# madiz_plate_sheet_v3_2.net
KiCad netlist of a schematic drawn in Altium Designer
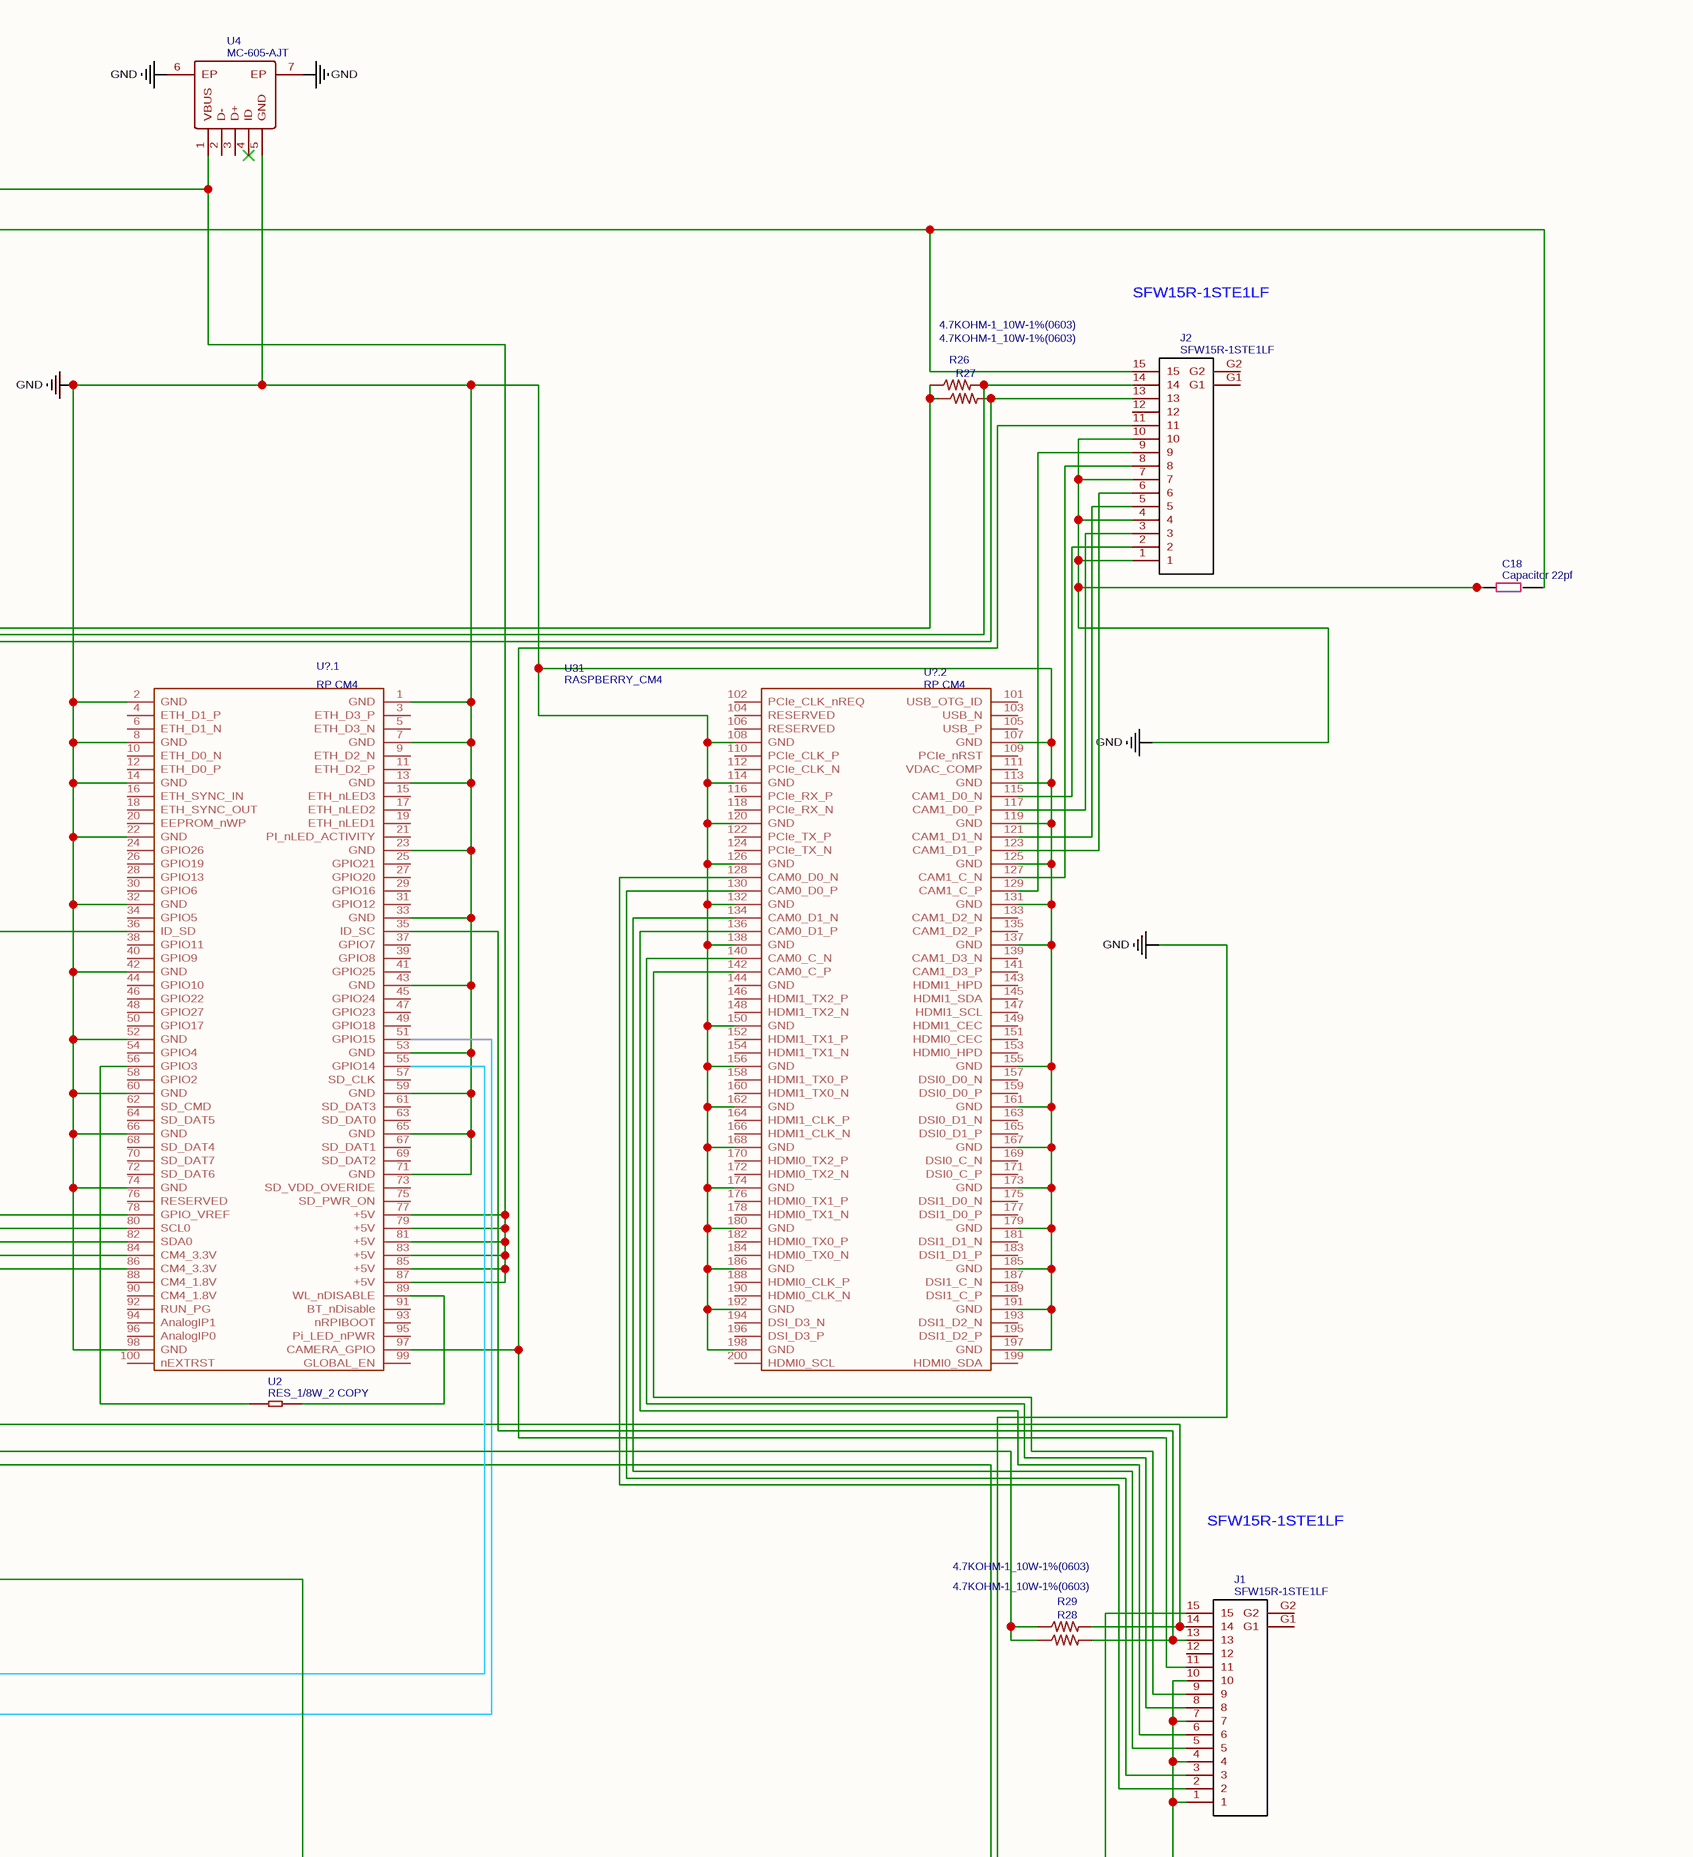
[diagram p0: madiz_plate_sheet_v3_2.schdoc, top right]
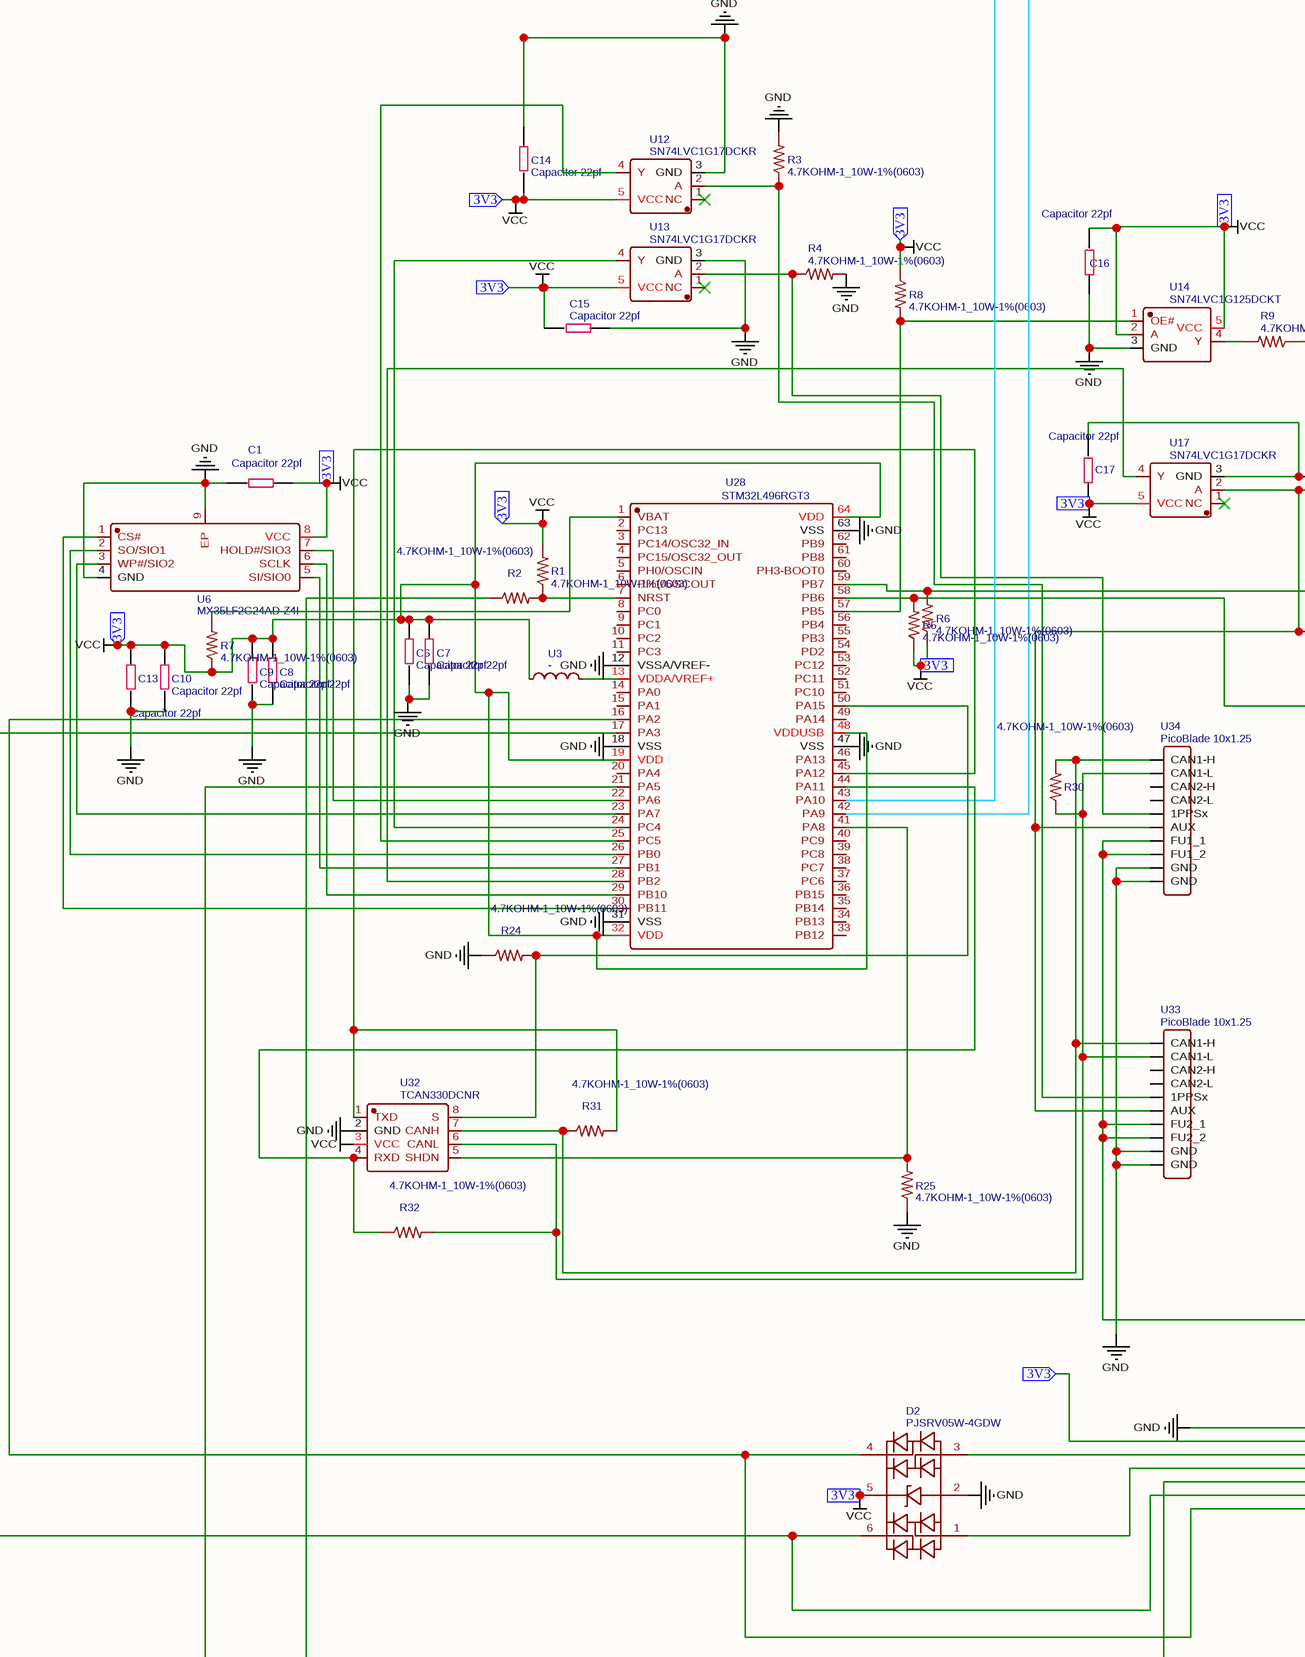
[diagram p1: madiz_plate_sheet_v3_2.schdoc, bottom left]
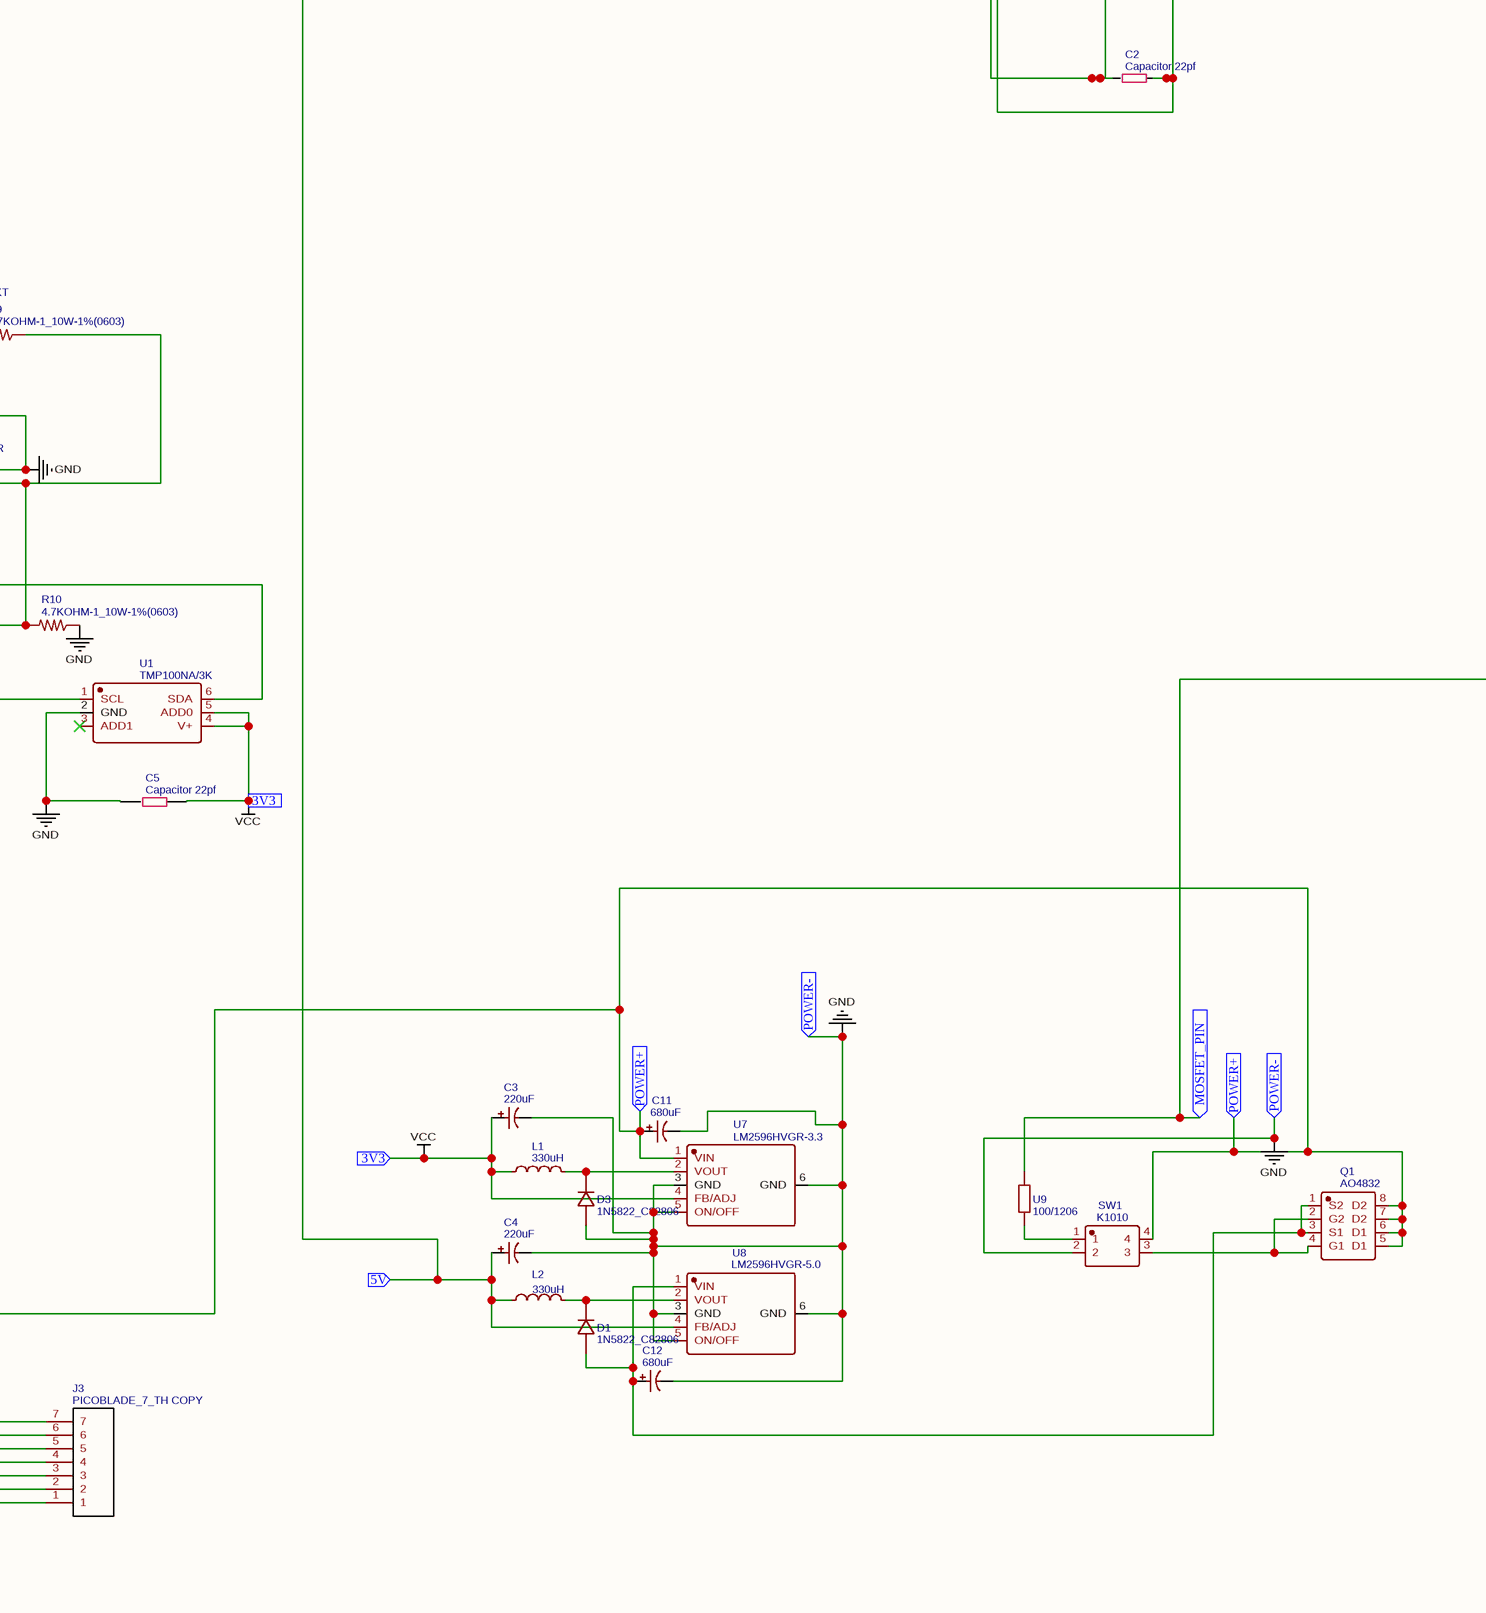
[diagram p2: madiz_plate_sheet_v3_2.schdoc, bottom right]

(export (version "E")
  (design (tool "Eeschema 10.0.6"))
  (components
    (comp (ref "C1")
      (value "Capacitor 22pf")
      (fields
        (field (name "MANUFACTURER") "KEMET")
        (field (name "MANUFACTURER PART") "C0805C220J5GACTU")
        (field (name "CONTRIBUTOR") "Tanay")
      )
      (libsource (lib "altium-import") (part "root_2_Capacitor 22pf_"))
    )
    (comp (ref "C2")
      (value "Capacitor 22pf")
      (fields
        (field (name "MANUFACTURER") "KEMET")
        (field (name "MANUFACTURER PART") "C0805C220J5GACTU")
        (field (name "CONTRIBUTOR") "Tanay")
      )
      (libsource (lib "altium-import") (part "root_2_Capacitor 22pf_"))
    )
    (comp (ref "C3")
      (value "220uF")
      (fields
        (field (name "MANUFACTURER") "CX(承兴)")
        (field (name "MANUFACTURER PART") "KS227M016F07RR0VH2FP0")
      )
      (libsource (lib "altium-import") (part "root_0_220uF_"))
    )
    (comp (ref "C4")
      (value "220uF")
      (fields
        (field (name "MANUFACTURER") "CX(承兴)")
        (field (name "MANUFACTURER PART") "KS227M016F07RR0VH2FP0")
      )
      (libsource (lib "altium-import") (part "root_0_220uF_"))
    )
    (comp (ref "C5")
      (value "Capacitor 22pf")
      (fields
        (field (name "MANUFACTURER") "KEMET")
        (field (name "MANUFACTURER PART") "C0805C220J5GACTU")
        (field (name "CONTRIBUTOR") "Tanay")
      )
      (libsource (lib "altium-import") (part "root_2_Capacitor 22pf_"))
    )
    (comp (ref "C6")
      (value "Capacitor 22pf")
      (fields
        (field (name "MANUFACTURER") "KEMET")
        (field (name "MANUFACTURER PART") "C0805C220J5GACTU")
        (field (name "CONTRIBUTOR") "Tanay")
      )
      (libsource (lib "altium-import") (part "root_3_Capacitor 22pf_"))
    )
    (comp (ref "C7")
      (value "Capacitor 22pf")
      (fields
        (field (name "MANUFACTURER") "KEMET")
        (field (name "MANUFACTURER PART") "C0805C220J5GACTU")
        (field (name "CONTRIBUTOR") "Tanay")
      )
      (libsource (lib "altium-import") (part "root_3_Capacitor 22pf_"))
    )
    (comp (ref "C8")
      (value "Capacitor 22pf")
      (fields
        (field (name "MANUFACTURER") "KEMET")
        (field (name "MANUFACTURER PART") "C0805C220J5GACTU")
        (field (name "CONTRIBUTOR") "Tanay")
      )
      (libsource (lib "altium-import") (part "root_3_Capacitor 22pf_"))
    )
    (comp (ref "C9")
      (value "Capacitor 22pf")
      (fields
        (field (name "MANUFACTURER") "KEMET")
        (field (name "MANUFACTURER PART") "C0805C220J5GACTU")
        (field (name "CONTRIBUTOR") "Tanay")
      )
      (libsource (lib "altium-import") (part "root_3_Capacitor 22pf_"))
    )
    (comp (ref "C10")
      (value "Capacitor 22pf")
      (fields
        (field (name "MANUFACTURER") "KEMET")
        (field (name "MANUFACTURER PART") "C0805C220J5GACTU")
        (field (name "CONTRIBUTOR") "Tanay")
      )
      (libsource (lib "altium-import") (part "root_3_Capacitor 22pf_"))
    )
    (comp (ref "C11")
      (value "680uF")
      (fields
        (field (name "MANUFACTURER") "CX(承兴)")
        (field (name "MANUFACTURER PART") "GR687M016F16RR0VL4FP0")
      )
      (libsource (lib "altium-import") (part "root_0_680uF_"))
    )
    (comp (ref "C12")
      (value "680uF")
      (fields
        (field (name "MANUFACTURER") "CX(承兴)")
        (field (name "MANUFACTURER PART") "GR687M016F16RR0VL4FP0")
      )
      (libsource (lib "altium-import") (part "root_0_680uF_"))
    )
    (comp (ref "C13")
      (value "Capacitor 22pf")
      (fields
        (field (name "MANUFACTURER") "KEMET")
        (field (name "MANUFACTURER PART") "C0805C220J5GACTU")
        (field (name "CONTRIBUTOR") "Tanay")
      )
      (libsource (lib "altium-import") (part "root_3_Capacitor 22pf_"))
    )
    (comp (ref "C14")
      (value "Capacitor 22pf")
      (fields
        (field (name "MANUFACTURER") "KEMET")
        (field (name "MANUFACTURER PART") "C0805C220J5GACTU")
        (field (name "CONTRIBUTOR") "Tanay")
      )
      (libsource (lib "altium-import") (part "root_3_Capacitor 22pf_"))
    )
    (comp (ref "C15")
      (value "Capacitor 22pf")
      (fields
        (field (name "MANUFACTURER") "KEMET")
        (field (name "MANUFACTURER PART") "C0805C220J5GACTU")
        (field (name "CONTRIBUTOR") "Tanay")
      )
      (libsource (lib "altium-import") (part "root_2_Capacitor 22pf_"))
    )
    (comp (ref "C16")
      (value "Capacitor 22pf")
      (fields
        (field (name "MANUFACTURER") "KEMET")
        (field (name "MANUFACTURER PART") "C0805C220J5GACTU")
        (field (name "CONTRIBUTOR") "Tanay")
      )
      (libsource (lib "altium-import") (part "root_1_Capacitor 22pf_"))
    )
    (comp (ref "C17")
      (value "Capacitor 22pf")
      (fields
        (field (name "MANUFACTURER") "KEMET")
        (field (name "MANUFACTURER PART") "C0805C220J5GACTU")
        (field (name "CONTRIBUTOR") "Tanay")
      )
      (libsource (lib "altium-import") (part "root_1_Capacitor 22pf_"))
    )
    (comp (ref "C18")
      (value "Capacitor 22pf")
      (fields
        (field (name "MANUFACTURER") "KEMET")
        (field (name "MANUFACTURER PART") "C0805C220J5GACTU")
        (field (name "CONTRIBUTOR") "Tanay")
      )
      (libsource (lib "altium-import") (part "root_0_Capacitor 22pf_"))
    )
    (comp (ref "D1")
      (value "1N5822_C82806")
      (fields (field (name "MANUFACTURER") "LRC(乐山无线电)") (field (name "MANUFACTURER PART") "1N5822"))
      (libsource (lib "altium-import") (part "root_3_1N5822_C82806_"))
    )
    (comp (ref "D2")
      (value "PJSRV05W-4GDW")
      (fields
        (field (name "MANUFACTURER") "PANJIT(强茂)")
        (field (name "MANUFACTURER PART") "PJSRV05W-4GDW_R1_00001")
        (field (name "CONTRIBUTOR") "LCSC")
      )
      (libsource (lib "altium-import") (part "root_1_PJSRV05W-4GDW_"))
    )
    (comp (ref "D3")
      (value "1N5822_C82806")
      (fields (field (name "MANUFACTURER") "LRC(乐山无线电)") (field (name "MANUFACTURER PART") "1N5822"))
      (libsource (lib "altium-import") (part "root_3_1N5822_C82806_"))
    )
    (comp (ref "J1")
      (value "SFW15R-1STE1LF")
      (fields (field (name "MANUFACTURER") "Amphenol FCI") (field (name "CONTRIBUTOR") "pietlgo221"))
      (libsource (lib "altium-import") (part "root_2_SFW15R-1STE1LF_"))
    )
    (comp (ref "J2")
      (value "SFW15R-1STE1LF")
      (fields (field (name "MANUFACTURER") "Amphenol FCI") (field (name "CONTRIBUTOR") "pietlgo221"))
      (libsource (lib "altium-import") (part "root_2_SFW15R-1STE1LF_"))
    )
    (comp (ref "J3")
      (value "PICOBLADE_7_TH COPY")
      (fields (field (name "MANUFACTURER PART") "0530481510") (field (name "CONTRIBUTOR") "henkmeid"))
      (libsource (lib "altium-import") (part "root_2_PICOBLADE_7_TH COPY_"))
    )
    (comp (ref "L1")
      (value "330uH")
      (fields
        (field (name "MANUFACTURER") "TDK")
        (field (name "MANUFACTURER PART") "B82477G4334M000")
        (field (name "CONTRIBUTOR") "lcsc")
      )
      (libsource (lib "altium-import") (part "root_0_330uH_"))
    )
    (comp (ref "L2")
      (value "330uH")
      (fields
        (field (name "MANUFACTURER") "TDK")
        (field (name "MANUFACTURER PART") "B82477G4334M000")
        (field (name "CONTRIBUTOR") "lcsc")
      )
      (libsource (lib "altium-import") (part "root_0_330uH_"))
    )
    (comp (ref "Q1")
      (value "AO4832")
      (fields (field (name "MANUFACTURER") "AOS") (field (name "CONTRIBUTOR") "LCSC"))
      (libsource (lib "altium-import") (part "root_0_AO4832_"))
    )
    (comp (ref "R1")
      (value "4.7KOHM-1_10W-1%(0603)")
      (description "RES-07857")
      (fields (field (name "CONTRIBUTOR") "SparkFun"))
      (libsource (lib "altium-import") (part "root_1_4.7KOHM-1_10W-1%(0603)_"))
    )
    (comp (ref "R2")
      (value "4.7KOHM-1_10W-1%(0603)")
      (description "RES-07857")
      (fields (field (name "CONTRIBUTOR") "SparkFun"))
      (libsource (lib "altium-import") (part "root_0_4.7KOHM-1_10W-1%(0603)_"))
    )
    (comp (ref "R3")
      (value "4.7KOHM-1_10W-1%(0603)")
      (description "RES-07857")
      (fields (field (name "CONTRIBUTOR") "SparkFun"))
      (libsource (lib "altium-import") (part "root_1_4.7KOHM-1_10W-1%(0603)_"))
    )
    (comp (ref "R4")
      (value "4.7KOHM-1_10W-1%(0603)")
      (description "RES-07857")
      (fields (field (name "CONTRIBUTOR") "SparkFun"))
      (libsource (lib "altium-import") (part "root_0_4.7KOHM-1_10W-1%(0603)_"))
    )
    (comp (ref "R5")
      (value "4.7KOHM-1_10W-1%(0603)")
      (description "RES-07857")
      (fields (field (name "CONTRIBUTOR") "SparkFun"))
      (libsource (lib "altium-import") (part "root_1_4.7KOHM-1_10W-1%(0603)_"))
    )
    (comp (ref "R6")
      (value "4.7KOHM-1_10W-1%(0603)")
      (description "RES-07857")
      (fields (field (name "CONTRIBUTOR") "SparkFun"))
      (libsource (lib "altium-import") (part "root_1_4.7KOHM-1_10W-1%(0603)_"))
    )
    (comp (ref "R7")
      (value "4.7KOHM-1_10W-1%(0603)")
      (description "RES-07857")
      (fields (field (name "CONTRIBUTOR") "SparkFun"))
      (libsource (lib "altium-import") (part "root_1_4.7KOHM-1_10W-1%(0603)_"))
    )
    (comp (ref "R8")
      (value "4.7KOHM-1_10W-1%(0603)")
      (description "RES-07857")
      (fields (field (name "CONTRIBUTOR") "SparkFun"))
      (libsource (lib "altium-import") (part "root_3_4.7KOHM-1_10W-1%(0603)_"))
    )
    (comp (ref "R9")
      (value "4.7KOHM-1_10W-1%(0603)")
      (description "RES-07857")
      (fields (field (name "CONTRIBUTOR") "SparkFun"))
      (libsource (lib "altium-import") (part "root_2_4.7KOHM-1_10W-1%(0603)_"))
    )
    (comp (ref "R10")
      (value "4.7KOHM-1_10W-1%(0603)")
      (description "RES-07857")
      (fields (field (name "CONTRIBUTOR") "SparkFun"))
      (libsource (lib "altium-import") (part "root_2_4.7KOHM-1_10W-1%(0603)_"))
    )
    (comp (ref "R24")
      (value "4.7KOHM-1_10W-1%(0603)")
      (description "RES-07857")
      (fields (field (name "CONTRIBUTOR") "SparkFun"))
      (libsource (lib "altium-import") (part "root_0_4.7KOHM-1_10W-1%(0603)_"))
    )
    (comp (ref "R25")
      (value "4.7KOHM-1_10W-1%(0603)")
      (description "RES-07857")
      (fields (field (name "CONTRIBUTOR") "SparkFun"))
      (libsource (lib "altium-import") (part "root_1_4.7KOHM-1_10W-1%(0603)_"))
    )
    (comp (ref "R26")
      (value "4.7KOHM-1_10W-1%(0603)")
      (description "RES-07857")
      (fields (field (name "CONTRIBUTOR") "SparkFun"))
      (libsource (lib "altium-import") (part "root_0_4.7KOHM-1_10W-1%(0603)_"))
    )
    (comp (ref "R27")
      (value "4.7KOHM-1_10W-1%(0603)")
      (description "RES-07857")
      (fields (field (name "CONTRIBUTOR") "SparkFun"))
      (libsource (lib "altium-import") (part "root_0_4.7KOHM-1_10W-1%(0603)_"))
    )
    (comp (ref "R28")
      (value "4.7KOHM-1_10W-1%(0603)")
      (description "RES-07857")
      (fields (field (name "CONTRIBUTOR") "SparkFun"))
      (libsource (lib "altium-import") (part "root_0_4.7KOHM-1_10W-1%(0603)_"))
    )
    (comp (ref "R29")
      (value "4.7KOHM-1_10W-1%(0603)")
      (description "RES-07857")
      (fields (field (name "CONTRIBUTOR") "SparkFun"))
      (libsource (lib "altium-import") (part "root_0_4.7KOHM-1_10W-1%(0603)_"))
    )
    (comp (ref "R30")
      (value "4.7KOHM-1_10W-1%(0603)")
      (description "RES-07857")
      (fields (field (name "CONTRIBUTOR") "SparkFun"))
      (libsource (lib "altium-import") (part "root_1_4.7KOHM-1_10W-1%(0603)_"))
    )
    (comp (ref "R31")
      (value "4.7KOHM-1_10W-1%(0603)")
      (description "RES-07857")
      (fields (field (name "CONTRIBUTOR") "SparkFun"))
      (libsource (lib "altium-import") (part "root_0_4.7KOHM-1_10W-1%(0603)_"))
    )
    (comp (ref "R32")
      (value "4.7KOHM-1_10W-1%(0603)")
      (description "RES-07857")
      (fields (field (name "CONTRIBUTOR") "SparkFun"))
      (libsource (lib "altium-import") (part "root_0_4.7KOHM-1_10W-1%(0603)_"))
    )
    (comp (ref "SW1")
      (value "K1010")
      (fields (field (name "MANUFACTURER") "Cosmo") (field (name "CONTRIBUTOR") "LCSC"))
      (libsource (lib "altium-import") (part "root_0_K1010_"))
    )
    (comp (ref "U1")
      (value "TMP100NA/3K")
      (fields (field (name "MANUFACTURER") "TI(德州仪器)"))
      (libsource (lib "altium-import") (part "root_0_TMP100NA/3K_"))
    )
    (comp (ref "U2")
      (value "RES_1/8W_2 COPY")
      (fields (field (name "CONTRIBUTOR") "Tonnam"))
      (libsource (lib "altium-import") (part "root_1_RES_1/8W_2 COPY_"))
    )
    (comp (ref "U3")
      (value "-")
      (fields (field (name "MANUFACTURER PART") "SDR0302-151KL") (field (name "CONTRIBUTOR") "LCSC"))
      (libsource (lib "altium-import") (part "root_0_-_"))
    )
    (comp (ref "U4")
      (value "MC-605-AJT")
      (fields (field (name "MANUFACTURER") "HANBO(汉博)") (field (name "CONTRIBUTOR") "lcsc"))
      (libsource (lib "altium-import") (part "root_1_MC-605-AJT_"))
    )
    (comp (ref "U6")
      (value "MX35LF2G24AD-Z4I")
      (fields (field (name "MANUFACTURER") "MXIC(旺宏电子)") (field (name "CONTRIBUTOR") "lcsc"))
      (libsource (lib "altium-import") (part "root_0_MX35LF2G24AD-Z4I_"))
    )
    (comp (ref "U7")
      (value "LM2596HVGR-3.3")
      (fields
        (field (name "MANUFACTURER") "HTC")
        (field (name "MANUFACTURER PART") "LM2596HVGR-5.0")
        (field (name "CONTRIBUTOR") "LCSC")
      )
      (libsource (lib "altium-import") (part "root_0_LM2596HVGR-3.3_"))
    )
    (comp (ref "U8")
      (value "LM2596HVGR-5.0")
      (fields (field (name "MANUFACTURER") "HTC") (field (name "CONTRIBUTOR") "LCSC"))
      (libsource (lib "altium-import") (part "root_0_LM2596HVGR-5.0_"))
    )
    (comp (ref "U9")
      (value "100/1206")
      (fields (field (name "MANUFACTURER PART") "1K2/1206") (field (name "CONTRIBUTOR") "lcsc"))
      (libsource (lib "altium-import") (part "root_1_100/1206_"))
    )
    (comp (ref "U12")
      (value "SN74LVC1G17DCKR")
      (fields (field (name "MANUFACTURER") "TI(德州仪器)"))
      (libsource (lib "altium-import") (part "root_1_SN74LVC1G17DCKR_"))
    )
    (comp (ref "U13")
      (value "SN74LVC1G17DCKR")
      (fields (field (name "MANUFACTURER") "TI(德州仪器)"))
      (libsource (lib "altium-import") (part "root_1_SN74LVC1G17DCKR_"))
    )
    (comp (ref "U14")
      (value "SN74LVC1G125DCKT")
      (fields (field (name "MANUFACTURER") "TI(德州仪器)") (field (name "CONTRIBUTOR") "LCSC"))
      (libsource (lib "altium-import") (part "root_0_SN74LVC1G125DCKT_"))
    )
    (comp (ref "U17")
      (value "SN74LVC1G17DCKR")
      (fields (field (name "MANUFACTURER") "TI(德州仪器)"))
      (libsource (lib "altium-import") (part "root_1_SN74LVC1G17DCKR_"))
    )
    (comp (ref "U28")
      (value "STM32L496RGT3")
      (fields (field (name "MANUFACTURER") "ST(意法半导体)") (field (name "CONTRIBUTOR") "LCSC"))
      (libsource (lib "altium-import") (part "root_0_STM32L496RGT3_"))
    )
    (comp (ref "U31")
      (value "RASPBERRY_CM4")
      (fields (field (name "CONTRIBUTOR") "neweirik"))
      (libsource (lib "altium-import") (part "root_0_RASPBERRY_CM4_"))
    )
    (comp (ref "U32")
      (value "TCAN330DCNR")
      (fields (field (name "MANUFACTURER") "TI(德州仪器)") (field (name "CONTRIBUTOR") "LCSC"))
      (libsource (lib "altium-import") (part "root_0_TCAN330DCNR_"))
    )
    (comp (ref "U33")
      (value "PicoBlade 10x1.25")
      (fields
        (field (name "MANUFACTURER") "Molex")
        (field (name "MANUFACTURER PART") "15134-1002")
        (field (name "CONTRIBUTOR") "jcanofuentes")
      )
      (libsource (lib "altium-import") (part "root_0_PicoBlade 10x1.25_"))
    )
    (comp (ref "U34")
      (value "PicoBlade 10x1.25")
      (fields
        (field (name "MANUFACTURER") "Molex")
        (field (name "MANUFACTURER PART") "15134-1002")
        (field (name "CONTRIBUTOR") "jcanofuentes")
      )
      (libsource (lib "altium-import") (part "root_0_PicoBlade 10x1.25_"))
    )
  )
  (nets
    (net (code "1") (name "/5V") (class "Default")
      (node (ref "C4") (pin "1") (pinfunction "1_1") (pintype "passive"))
      (node (ref "L2") (pin "1") (pinfunction "1_1") (pintype "passive"))
      (node (ref "U31") (pin "77") (pinfunction "+5V_77") (pintype "passive"))
      (node (ref "U31") (pin "79") (pinfunction "+5V_79") (pintype "passive"))
      (node (ref "U31") (pin "81") (pinfunction "+5V_81") (pintype "passive"))
      (node (ref "U31") (pin "83") (pinfunction "+5V_83") (pintype "passive"))
      (node (ref "U31") (pin "85") (pinfunction "+5V_85") (pintype "passive"))
      (node (ref "U31") (pin "87") (pinfunction "+5V_87") (pintype "passive"))
      (node (ref "U4") (pin "1") (pinfunction "VBUS_1") (pintype "passive"))
      (node (ref "U8") (pin "4") (pinfunction "FB/ADJ_4") (pintype "passive"))
    )
    (net (code "2") (name "/MOSFET_PIN") (class "Default")
      (node (ref "U28") (pin "21") (pinfunction "PA5_21") (pintype "passive"))
      (node (ref "U9") (pin "2") (pinfunction "2_2") (pintype "passive"))
    )
    (net (code "3") (name "/POWER+") (class "Default")
      (node (ref "C11") (pin "1") (pinfunction "1_1") (pintype "passive"))
      (node (ref "Q1") (pin "5") (pinfunction "D1_5") (pintype "passive"))
      (node (ref "Q1") (pin "6") (pinfunction "D1_6") (pintype "passive"))
      (node (ref "Q1") (pin "7") (pinfunction "D2_7") (pintype "passive"))
      (node (ref "Q1") (pin "8") (pinfunction "D2_8") (pintype "passive"))
      (node (ref "SW1") (pin "4") (pinfunction "4_4") (pintype "passive"))
      (node (ref "U33") (pin "7") (pinfunction "FU1_1_7") (pintype "passive"))
      (node (ref "U33") (pin "8") (pinfunction "FU1_2_8") (pintype "passive"))
      (node (ref "U34") (pin "7") (pinfunction "FU1_1_7") (pintype "passive"))
      (node (ref "U34") (pin "8") (pinfunction "FU1_2_8") (pintype "passive"))
      (node (ref "U7") (pin "1") (pinfunction "VIN_1") (pintype "passive"))
    )
    (net (code "4") (name "GND") (class "Default")
      (node (ref "C1") (pin "2") (pinfunction "2_2") (pintype "passive"))
      (node (ref "C10") (pin "2") (pinfunction "2_2") (pintype "passive"))
      (node (ref "C11") (pin "2") (pinfunction "2_2") (pintype "passive"))
      (node (ref "C12") (pin "2") (pinfunction "2_2") (pintype "passive"))
      (node (ref "C13") (pin "2") (pinfunction "2_2") (pintype "passive"))
      (node (ref "C14") (pin "1") (pinfunction "1_1") (pintype "passive"))
      (node (ref "C15") (pin "1") (pinfunction "1_1") (pintype "passive"))
      (node (ref "C16") (pin "1") (pinfunction "1_1") (pintype "passive"))
      (node (ref "C17") (pin "2") (pinfunction "2_2") (pintype "passive"))
      (node (ref "C18") (pin "1") (pinfunction "1_1") (pintype "passive"))
      (node (ref "C2") (pin "1") (pinfunction "1_1") (pintype "passive"))
      (node (ref "C3") (pin "2") (pinfunction "2_2") (pintype "passive"))
      (node (ref "C4") (pin "2") (pinfunction "2_2") (pintype "passive"))
      (node (ref "C5") (pin "2") (pinfunction "2_2") (pintype "passive"))
      (node (ref "C6") (pin "2") (pinfunction "2_2") (pintype "passive"))
      (node (ref "C7") (pin "2") (pinfunction "2_2") (pintype "passive"))
      (node (ref "C8") (pin "2") (pinfunction "2_2") (pintype "passive"))
      (node (ref "C9") (pin "2") (pinfunction "2_2") (pintype "passive"))
      (node (ref "D2") (pin "2") (pinfunction "2_2") (pintype "passive"))
      (node (ref "D3") (pin "2") (pinfunction "A_2") (pintype "passive"))
      (node (ref "J1") (pin "1") (pinfunction "1_1") (pintype "passive"))
      (node (ref "J1") (pin "10") (pinfunction "10_10") (pintype "passive"))
      (node (ref "J1") (pin "4") (pinfunction "4_4") (pintype "passive"))
      (node (ref "J1") (pin "7") (pinfunction "7_7") (pintype "passive"))
      (node (ref "J2") (pin "1") (pinfunction "1_1") (pintype "passive"))
      (node (ref "J2") (pin "10") (pinfunction "10_10") (pintype "passive"))
      (node (ref "J2") (pin "4") (pinfunction "4_4") (pintype "passive"))
      (node (ref "J2") (pin "7") (pinfunction "7_7") (pintype "passive"))
      (node (ref "J3") (pin "7") (pinfunction "7_7") (pintype "passive"))
      (node (ref "R10") (pin "1") (pinfunction "1_1") (pintype "passive"))
      (node (ref "R24") (pin "1") (pinfunction "1_1") (pintype "passive"))
      (node (ref "R25") (pin "1") (pinfunction "1_1") (pintype "passive"))
      (node (ref "R3") (pin "2") (pinfunction "2_2") (pintype "passive"))
      (node (ref "R4") (pin "2") (pinfunction "2_2") (pintype "passive"))
      (node (ref "SW1") (pin "2") (pinfunction "2_2") (pintype "passive"))
      (node (ref "U1") (pin "2") (pinfunction "GND_2") (pintype "passive"))
      (node (ref "U12") (pin "3") (pinfunction "GND_3") (pintype "passive"))
      (node (ref "U13") (pin "3") (pinfunction "GND_3") (pintype "passive"))
      (node (ref "U14") (pin "3") (pinfunction "GND_3") (pintype "passive"))
      (node (ref "U17") (pin "3") (pinfunction "GND_3") (pintype "passive"))
      (node (ref "U28") (pin "12") (pinfunction "VSSA/VREF-_12") (pintype "passive"))
      (node (ref "U28") (pin "18") (pinfunction "VSS_18") (pintype "passive"))
      (node (ref "U28") (pin "31") (pinfunction "VSS_31") (pintype "passive"))
      (node (ref "U28") (pin "47") (pinfunction "VSS_47") (pintype "passive"))
      (node (ref "U28") (pin "63") (pinfunction "VSS_63") (pintype "passive"))
      (node (ref "U31") (pin "1") (pinfunction "GND_1") (pintype "passive"))
      (node (ref "U31") (pin "107") (pinfunction "GND_107") (pintype "passive"))
      (node (ref "U31") (pin "108") (pinfunction "GND_108") (pintype "passive"))
      (node (ref "U31") (pin "113") (pinfunction "GND_113") (pintype "passive"))
      (node (ref "U31") (pin "114") (pinfunction "GND_114") (pintype "passive"))
      (node (ref "U31") (pin "119") (pinfunction "GND_119") (pintype "passive"))
      (node (ref "U31") (pin "120") (pinfunction "GND_120") (pintype "passive"))
      (node (ref "U31") (pin "125") (pinfunction "GND_125") (pintype "passive"))
      (node (ref "U31") (pin "126") (pinfunction "GND_126") (pintype "passive"))
      (node (ref "U31") (pin "13") (pinfunction "GND_13") (pintype "passive"))
      (node (ref "U31") (pin "131") (pinfunction "GND_131") (pintype "passive"))
      (node (ref "U31") (pin "132") (pinfunction "GND_132") (pintype "passive"))
      (node (ref "U31") (pin "137") (pinfunction "GND_137") (pintype "passive"))
      (node (ref "U31") (pin "138") (pinfunction "GND_138") (pintype "passive"))
      (node (ref "U31") (pin "14") (pinfunction "GND_14") (pintype "passive"))
      (node (ref "U31") (pin "150") (pinfunction "GND_150") (pintype "passive"))
      (node (ref "U31") (pin "155") (pinfunction "GND_155") (pintype "passive"))
      (node (ref "U31") (pin "156") (pinfunction "GND_156") (pintype "passive"))
      (node (ref "U31") (pin "161") (pinfunction "GND_161") (pintype "passive"))
      (node (ref "U31") (pin "162") (pinfunction "GND_162") (pintype "passive"))
      (node (ref "U31") (pin "167") (pinfunction "GND_167") (pintype "passive"))
      (node (ref "U31") (pin "168") (pinfunction "GND_168") (pintype "passive"))
      (node (ref "U31") (pin "173") (pinfunction "GND_173") (pintype "passive"))
      (node (ref "U31") (pin "174") (pinfunction "GND_174") (pintype "passive"))
      (node (ref "U31") (pin "179") (pinfunction "GND_179") (pintype "passive"))
      (node (ref "U31") (pin "180") (pinfunction "GND_180") (pintype "passive"))
      (node (ref "U31") (pin "185") (pinfunction "GND_185") (pintype "passive"))
      (node (ref "U31") (pin "186") (pinfunction "GND_186") (pintype "passive"))
      (node (ref "U31") (pin "191") (pinfunction "GND_191") (pintype "passive"))
      (node (ref "U31") (pin "192") (pinfunction "GND_192") (pintype "passive"))
      (node (ref "U31") (pin "197") (pinfunction "GND_197") (pintype "passive"))
      (node (ref "U31") (pin "198") (pinfunction "GND_198") (pintype "passive"))
      (node (ref "U31") (pin "2") (pinfunction "GND_2") (pintype "passive"))
      (node (ref "U31") (pin "22") (pinfunction "GND_22") (pintype "passive"))
      (node (ref "U31") (pin "23") (pinfunction "GND_23") (pintype "passive"))
      (node (ref "U31") (pin "32") (pinfunction "GND_32") (pintype "passive"))
      (node (ref "U31") (pin "33") (pinfunction "GND_33") (pintype "passive"))
      (node (ref "U31") (pin "42") (pinfunction "GND_42") (pintype "passive"))
      (node (ref "U31") (pin "43") (pinfunction "GND_43") (pintype "passive"))
      (node (ref "U31") (pin "52") (pinfunction "GND_52") (pintype "passive"))
      (node (ref "U31") (pin "53") (pinfunction "GND_53") (pintype "passive"))
      (node (ref "U31") (pin "59") (pinfunction "GND_59") (pintype "passive"))
      (node (ref "U31") (pin "60") (pinfunction "GND_60") (pintype "passive"))
      (node (ref "U31") (pin "65") (pinfunction "GND_65") (pintype "passive"))
      (node (ref "U31") (pin "66") (pinfunction "GND_66") (pintype "passive"))
      (node (ref "U31") (pin "7") (pinfunction "GND_7") (pintype "passive"))
      (node (ref "U31") (pin "71") (pinfunction "GND_71") (pintype "passive"))
      (node (ref "U31") (pin "74") (pinfunction "GND_74") (pintype "passive"))
      (node (ref "U31") (pin "8") (pinfunction "GND_8") (pintype "passive"))
      (node (ref "U31") (pin "98") (pinfunction "GND_98") (pintype "passive"))
      (node (ref "U32") (pin "2") (pinfunction "GND_2") (pintype "passive"))
      (node (ref "U33") (pin "10") (pinfunction "GND_10") (pintype "passive"))
      (node (ref "U33") (pin "9") (pinfunction "GND_9") (pintype "passive"))
      (node (ref "U34") (pin "10") (pinfunction "GND_10") (pintype "passive"))
      (node (ref "U34") (pin "9") (pinfunction "GND_9") (pintype "passive"))
      (node (ref "U4") (pin "5") (pinfunction "GND_5") (pintype "passive"))
      (node (ref "U4") (pin "6") (pinfunction "EP_6") (pintype "passive"))
      (node (ref "U4") (pin "7") (pinfunction "EP_7") (pintype "passive"))
      (node (ref "U6") (pin "4") (pinfunction "GND_4") (pintype "passive"))
      (node (ref "U6") (pin "9") (pinfunction "EP_9") (pintype "passive"))
      (node (ref "U7") (pin "3") (pinfunction "GND_3") (pintype "passive"))
      (node (ref "U7") (pin "5") (pinfunction "ON/OFF_5") (pintype "passive"))
      (node (ref "U7") (pin "6") (pinfunction "GND_6") (pintype "passive"))
      (node (ref "U8") (pin "3") (pinfunction "GND_3") (pintype "passive"))
      (node (ref "U8") (pin "5") (pinfunction "ON/OFF_5") (pintype "passive"))
      (node (ref "U8") (pin "6") (pinfunction "GND_6") (pintype "passive"))
    )
    (net (code "5") (name "Net-(C2-Pad2)") (class "Default")
      (node (ref "C2") (pin "2") (pinfunction "2_2") (pintype "passive"))
      (node (ref "J1") (pin "15") (pinfunction "15_15") (pintype "passive"))
      (node (ref "U31") (pin "86") (pinfunction "CM4_3.3V_86") (pintype "passive"))
    )
    (net (code "6") (name "Net-(C18-Pad2)") (class "Default")
      (node (ref "C18") (pin "2") (pinfunction "2_2") (pintype "passive"))
      (node (ref "J2") (pin "15") (pinfunction "15_15") (pintype "passive"))
      (node (ref "U31") (pin "84") (pinfunction "CM4_3.3V_84") (pintype "passive"))
    )
    (net (code "7") (name "Net-(D1-A)") (class "Default")
      (node (ref "C12") (pin "1") (pinfunction "1_1") (pintype "passive"))
      (node (ref "D1") (pin "2") (pinfunction "A_2") (pintype "passive"))
      (node (ref "Q1") (pin "1") (pinfunction "S2_1") (pintype "passive"))
      (node (ref "Q1") (pin "3") (pinfunction "S1_3") (pintype "passive"))
      (node (ref "U8") (pin "1") (pinfunction "VIN_1") (pintype "passive"))
    )
    (net (code "8") (name "Net-(D1-C)") (class "Default")
      (node (ref "D1") (pin "1") (pinfunction "C_1") (pintype "passive"))
      (node (ref "L2") (pin "2") (pinfunction "2_2") (pintype "passive"))
      (node (ref "U8") (pin "2") (pinfunction "VOUT_2") (pintype "passive"))
    )
    (net (code "9") (name "Net-(D2-Pad1)") (class "Default")
      (node (ref "D2") (pin "1") (pinfunction "1_1") (pintype "passive"))
      (node (ref "J3") (pin "4") (pinfunction "4_4") (pintype "passive"))
    )
    (net (code "10") (name "Net-(D2-Pad3)") (class "Default")
      (node (ref "D2") (pin "3") (pinfunction "3_3") (pintype "passive"))
      (node (ref "J3") (pin "5") (pinfunction "5_5") (pintype "passive"))
    )
    (net (code "11") (name "Net-(D3-C)") (class "Default")
      (node (ref "D3") (pin "1") (pinfunction "C_1") (pintype "passive"))
      (node (ref "L1") (pin "2") (pinfunction "2_2") (pintype "passive"))
      (node (ref "U7") (pin "2") (pinfunction "VOUT_2") (pintype "passive"))
    )
    (net (code "12") (name "Net-(J3-Pad3)") (class "Default")
      (node (ref "J3") (pin "3") (pinfunction "3_3") (pintype "passive"))
      (node (ref "R2") (pin "1") (pinfunction "1_1") (pintype "passive"))
    )
    (net (code "13") (name "Net-(Q1-G1)") (class "Default")
      (node (ref "Q1") (pin "2") (pinfunction "G2_2") (pintype "passive"))
      (node (ref "Q1") (pin "4") (pinfunction "G1_4") (pintype "passive"))
      (node (ref "SW1") (pin "3") (pinfunction "3_3") (pintype "passive"))
    )
    (net (code "14") (name "Net-(SW1-Pad1)") (class "Default")
      (node (ref "SW1") (pin "1") (pinfunction "1_1") (pintype "passive"))
      (node (ref "U9") (pin "1") (pinfunction "1_1") (pintype "passive"))
    )
    (net (code "15") (name "Net-(U1-SCL)") (class "Default")
      (node (ref "R5") (pin "2") (pinfunction "2_2") (pintype "passive"))
      (node (ref "U1") (pin "1") (pinfunction "SCL_1") (pintype "passive"))
      (node (ref "U28") (pin "58") (pinfunction "PB6_58") (pintype "passive"))
    )
    (net (code "16") (name "Net-(U1-SDA)") (class "Default")
      (node (ref "R6") (pin "2") (pinfunction "2_2") (pintype "passive"))
      (node (ref "U1") (pin "6") (pinfunction "SDA_6") (pintype "passive"))
      (node (ref "U28") (pin "59") (pinfunction "PB7_59") (pintype "passive"))
    )
    (net (code "17") (name "Net-(U12-A)") (class "Default")
      (node (ref "R3") (pin "1") (pinfunction "1_1") (pintype "passive"))
      (node (ref "U12") (pin "2") (pinfunction "A_2") (pintype "passive"))
      (node (ref "U33") (pin "5") (pinfunction "1PPSx_5") (pintype "passive"))
    )
    (net (code "18") (name "Net-(U12-Y)") (class "Default")
      (node (ref "U12") (pin "4") (pinfunction "Y_4") (pintype "passive"))
      (node (ref "U28") (pin "25") (pinfunction "PC5_25") (pintype "passive"))
    )
    (net (code "19") (name "Net-(U13-A)") (class "Default")
      (node (ref "R4") (pin "1") (pinfunction "1_1") (pintype "passive"))
      (node (ref "U13") (pin "2") (pinfunction "A_2") (pintype "passive"))
      (node (ref "U34") (pin "5") (pinfunction "1PPSx_5") (pintype "passive"))
    )
    (net (code "20") (name "Net-(U13-Y)") (class "Default")
      (node (ref "U13") (pin "4") (pinfunction "Y_4") (pintype "passive"))
      (node (ref "U28") (pin "24") (pinfunction "PC4_24") (pintype "passive"))
    )
    (net (code "21") (name "Net-(U14-OE#)") (class "Default")
      (node (ref "R8") (pin "2") (pinfunction "2_2") (pintype "passive"))
      (node (ref "U14") (pin "1") (pinfunction "OE#_1") (pintype "passive"))
      (node (ref "U28") (pin "57") (pinfunction "PB5_57") (pintype "passive"))
    )
    (net (code "22") (name "Net-(U14-Y)") (class "Default")
      (node (ref "R9") (pin "2") (pinfunction "2_2") (pintype "passive"))
      (node (ref "U14") (pin "4") (pinfunction "Y_4") (pintype "passive"))
    )
    (net (code "23") (name "Net-(U17-A)") (class "Default")
      (node (ref "R10") (pin "2") (pinfunction "2_2") (pintype "passive"))
      (node (ref "R9") (pin "1") (pinfunction "1_1") (pintype "passive"))
      (node (ref "U17") (pin "2") (pinfunction "A_2") (pintype "passive"))
      (node (ref "U33") (pin "6") (pinfunction "AUX_6") (pintype "passive"))
      (node (ref "U34") (pin "6") (pinfunction "AUX_6") (pintype "passive"))
    )
    (net (code "24") (name "Net-(U17-Y)") (class "Default")
      (node (ref "U17") (pin "4") (pinfunction "Y_4") (pintype "passive"))
      (node (ref "U28") (pin "28") (pinfunction "PB2_28") (pintype "passive"))
    )
    (net (code "25") (name "Net-(U28-NRST)") (class "Default")
      (node (ref "R1") (pin "1") (pinfunction "1_1") (pintype "passive"))
      (node (ref "R2") (pin "2") (pinfunction "2_2") (pintype "passive"))
      (node (ref "U28") (pin "7") (pinfunction "NRST_7") (pintype "passive"))
    )
    (net (code "26") (name "Net-(U28-PA2)") (class "Default")
      (node (ref "D2") (pin "4") (pinfunction "4_4") (pintype "passive"))
      (node (ref "J3") (pin "1") (pinfunction "1_1") (pintype "passive"))
      (node (ref "U28") (pin "16") (pinfunction "PA2_16") (pintype "passive"))
    )
    (net (code "27") (name "Net-(U28-PA3)") (class "Default")
      (node (ref "D2") (pin "6") (pinfunction "6_6") (pintype "passive"))
      (node (ref "J3") (pin "2") (pinfunction "2_2") (pintype "passive"))
      (node (ref "U28") (pin "17") (pinfunction "PA3_17") (pintype "passive"))
    )
    (net (code "28") (name "Net-(U28-PA6)") (class "Default")
      (node (ref "U28") (pin "22") (pinfunction "PA6_22") (pintype "passive"))
      (node (ref "U6") (pin "7") (pinfunction "HOLD#/SIO3_7") (pintype "passive"))
    )
    (net (code "29") (name "Net-(U28-PA7)") (class "Default")
      (node (ref "U28") (pin "23") (pinfunction "PA7_23") (pintype "passive"))
      (node (ref "U6") (pin "3") (pinfunction "WP#/SIO2_3") (pintype "passive"))
    )
    (net (code "30") (name "Net-(U28-PA8)") (class "Default")
      (node (ref "R25") (pin "2") (pinfunction "2_2") (pintype "passive"))
      (node (ref "U28") (pin "41") (pinfunction "PA8_41") (pintype "passive"))
      (node (ref "U32") (pin "5") (pinfunction "SHDN_5") (pintype "passive"))
    )
    (net (code "31") (name "Net-(U28-PA9)") (class "Default")
      (node (ref "U28") (pin "42") (pinfunction "PA9_42") (pintype "passive"))
      (node (ref "U31") (pin "51") (pinfunction "GPIO15_51") (pintype "passive"))
    )
    (net (code "32") (name "Net-(U28-PA10)") (class "Default")
      (node (ref "U28") (pin "43") (pinfunction "PA10_43") (pintype "passive"))
      (node (ref "U31") (pin "55") (pinfunction "GPIO14_55") (pintype "passive"))
    )
    (net (code "33") (name "Net-(U28-PA11)") (class "Default")
      (node (ref "R32") (pin "1") (pinfunction "1_1") (pintype "passive"))
      (node (ref "U28") (pin "44") (pinfunction "PA11_44") (pintype "passive"))
      (node (ref "U32") (pin "4") (pinfunction "RXD_4") (pintype "passive"))
    )
    (net (code "34") (name "Net-(U28-PA12)") (class "Default")
      (node (ref "R31") (pin "2") (pinfunction "2_2") (pintype "passive"))
      (node (ref "U28") (pin "45") (pinfunction "PA12_45") (pintype "passive"))
      (node (ref "U32") (pin "1") (pinfunction "TXD_1") (pintype "passive"))
    )
    (net (code "35") (name "Net-(U28-PA15)") (class "Default")
      (node (ref "R24") (pin "2") (pinfunction "2_2") (pintype "passive"))
      (node (ref "U28") (pin "50") (pinfunction "PA15_50") (pintype "passive"))
      (node (ref "U32") (pin "8") (pinfunction "S_8") (pintype "passive"))
    )
    (net (code "36") (name "Net-(U28-PB0)") (class "Default")
      (node (ref "U28") (pin "26") (pinfunction "PB0_26") (pintype "passive"))
      (node (ref "U6") (pin "2") (pinfunction "SO/SIO1_2") (pintype "passive"))
    )
    (net (code "37") (name "Net-(U28-PB1)") (class "Default")
      (node (ref "U28") (pin "27") (pinfunction "PB1_27") (pintype "passive"))
      (node (ref "U6") (pin "5") (pinfunction "SI/SIO0_5") (pintype "passive"))
    )
    (net (code "38") (name "Net-(U28-PB10)") (class "Default")
      (node (ref "U28") (pin "29") (pinfunction "PB10_29") (pintype "passive"))
      (node (ref "U6") (pin "6") (pinfunction "SCLK_6") (pintype "passive"))
    )
    (net (code "39") (name "Net-(U28-PB11)") (class "Default")
      (node (ref "U28") (pin "30") (pinfunction "PB11_30") (pintype "passive"))
      (node (ref "U6") (pin "1") (pinfunction "CS#_1") (pintype "passive"))
    )
    (net (code "40") (name "Net-(U28-VBAT)") (class "Default")
      (node (ref "R7") (pin "2") (pinfunction "2_2") (pintype "passive"))
      (node (ref "U28") (pin "1") (pinfunction "VBAT_1") (pintype "passive"))
    )
    (net (code "41") (name "Net-(U28-VDDA{slash}VREF+)") (class "Default")
      (node (ref "U28") (pin "13") (pinfunction "VDDA/VREF+_13") (pintype "passive"))
      (node (ref "U3") (pin "2") (pinfunction "2_2") (pintype "passive"))
    )
    (net (code "42") (name "Net-(U31-CAM0_C_N)") (class "Default")
      (node (ref "J1") (pin "8") (pinfunction "8_8") (pintype "passive"))
      (node (ref "U31") (pin "140") (pinfunction "CAM0_C_N_140") (pintype "passive"))
    )
    (net (code "43") (name "Net-(U31-CAM0_C_P)") (class "Default")
      (node (ref "J1") (pin "9") (pinfunction "9_9") (pintype "passive"))
      (node (ref "U31") (pin "142") (pinfunction "CAM0_C_P_142") (pintype "passive"))
    )
    (net (code "44") (name "Net-(U31-CAM0_D0_N)") (class "Default")
      (node (ref "J1") (pin "2") (pinfunction "2_2") (pintype "passive"))
      (node (ref "U31") (pin "128") (pinfunction "CAM0_D0_N_128") (pintype "passive"))
    )
    (net (code "45") (name "Net-(U31-CAM0_D0_P)") (class "Default")
      (node (ref "J1") (pin "3") (pinfunction "3_3") (pintype "passive"))
      (node (ref "U31") (pin "130") (pinfunction "CAM0_D0_P_130") (pintype "passive"))
    )
    (net (code "46") (name "Net-(U31-CAM0_D1_N)") (class "Default")
      (node (ref "J1") (pin "5") (pinfunction "5_5") (pintype "passive"))
      (node (ref "U31") (pin "134") (pinfunction "CAM0_D1_N_134") (pintype "passive"))
    )
    (net (code "47") (name "Net-(U31-CAM0_D1_P)") (class "Default")
      (node (ref "J1") (pin "6") (pinfunction "6_6") (pintype "passive"))
      (node (ref "U31") (pin "136") (pinfunction "CAM0_D1_P_136") (pintype "passive"))
    )
    (net (code "48") (name "Net-(U31-CAM1_C_N)") (class "Default")
      (node (ref "J2") (pin "8") (pinfunction "8_8") (pintype "passive"))
      (node (ref "U31") (pin "127") (pinfunction "CAM1_C_N_127") (pintype "passive"))
    )
    (net (code "49") (name "Net-(U31-CAM1_C_P)") (class "Default")
      (node (ref "J2") (pin "9") (pinfunction "9_9") (pintype "passive"))
      (node (ref "U31") (pin "129") (pinfunction "CAM1_C_P_129") (pintype "passive"))
    )
    (net (code "50") (name "Net-(U31-CAM1_D0_N)") (class "Default")
      (node (ref "J2") (pin "2") (pinfunction "2_2") (pintype "passive"))
      (node (ref "U31") (pin "115") (pinfunction "CAM1_D0_N_115") (pintype "passive"))
    )
    (net (code "51") (name "Net-(U31-CAM1_D0_P)") (class "Default")
      (node (ref "J2") (pin "3") (pinfunction "3_3") (pintype "passive"))
      (node (ref "U31") (pin "117") (pinfunction "CAM1_D0_P_117") (pintype "passive"))
    )
    (net (code "52") (name "Net-(U31-CAM1_D1_N)") (class "Default")
      (node (ref "J2") (pin "5") (pinfunction "5_5") (pintype "passive"))
      (node (ref "U31") (pin "121") (pinfunction "CAM1_D1_N_121") (pintype "passive"))
    )
    (net (code "53") (name "Net-(U31-CAM1_D1_P)") (class "Default")
      (node (ref "J2") (pin "6") (pinfunction "6_6") (pintype "passive"))
      (node (ref "U31") (pin "123") (pinfunction "CAM1_D1_P_123") (pintype "passive"))
    )
    (net (code "54") (name "Net-(U31-CAMERA_GPIO)") (class "Default")
      (node (ref "J1") (pin "11") (pinfunction "11_11") (pintype "passive"))
      (node (ref "J2") (pin "11") (pinfunction "11_11") (pintype "passive"))
      (node (ref "U31") (pin "97") (pinfunction "CAMERA_GPIO_97") (pintype "passive"))
    )
    (net (code "55") (name "Net-(U31-GPIO3)") (class "Default")
      (node (ref "U2") (pin "1") (pinfunction "1_1") (pintype "passive"))
      (node (ref "U31") (pin "56") (pinfunction "GPIO3_56") (pintype "passive"))
    )
    (net (code "56") (name "Net-(U31-GPIO_VREF)") (class "Default")
      (node (ref "R26") (pin "1") (pinfunction "1_1") (pintype "passive"))
      (node (ref "R27") (pin "1") (pinfunction "1_1") (pintype "passive"))
      (node (ref "R28") (pin "1") (pinfunction "1_1") (pintype "passive"))
      (node (ref "R29") (pin "1") (pinfunction "1_1") (pintype "passive"))
      (node (ref "U31") (pin "78") (pinfunction "GPIO_VREF_78") (pintype "passive"))
    )
    (net (code "57") (name "Net-(U31-ID_SC)") (class "Default")
      (node (ref "J1") (pin "13") (pinfunction "13_13") (pintype "passive"))
      (node (ref "R28") (pin "2") (pinfunction "2_2") (pintype "passive"))
      (node (ref "U31") (pin "35") (pinfunction "ID_SC_35") (pintype "passive"))
    )
    (net (code "58") (name "Net-(U31-ID_SD)") (class "Default")
      (node (ref "J1") (pin "14") (pinfunction "14_14") (pintype "passive"))
      (node (ref "R29") (pin "2") (pinfunction "2_2") (pintype "passive"))
      (node (ref "U31") (pin "36") (pinfunction "ID_SD_36") (pintype "passive"))
    )
    (net (code "59") (name "Net-(U31-SCL0)") (class "Default")
      (node (ref "J2") (pin "13") (pinfunction "13_13") (pintype "passive"))
      (node (ref "R27") (pin "2") (pinfunction "2_2") (pintype "passive"))
      (node (ref "U31") (pin "80") (pinfunction "SCL0_80") (pintype "passive"))
    )
    (net (code "60") (name "Net-(U31-SDA0)") (class "Default")
      (node (ref "J2") (pin "14") (pinfunction "14_14") (pintype "passive"))
      (node (ref "R26") (pin "2") (pinfunction "2_2") (pintype "passive"))
      (node (ref "U31") (pin "82") (pinfunction "SDA0_82") (pintype "passive"))
    )
    (net (code "61") (name "Net-(U31-WL_nDISABLE)") (class "Default")
      (node (ref "U2") (pin "2") (pinfunction "2_2") (pintype "passive"))
      (node (ref "U31") (pin "89") (pinfunction "WL_nDISABLE_89") (pintype "passive"))
    )
    (net (code "62") (name "Net-(U32-CANH)") (class "Default")
      (node (ref "R30") (pin "2") (pinfunction "2_2") (pintype "passive"))
      (node (ref "R31") (pin "1") (pinfunction "1_1") (pintype "passive"))
      (node (ref "U32") (pin "7") (pinfunction "CANH_7") (pintype "passive"))
      (node (ref "U33") (pin "1") (pinfunction "CAN1-H_1") (pintype "passive"))
      (node (ref "U34") (pin "1") (pinfunction "CAN1-H_1") (pintype "passive"))
    )
    (net (code "63") (name "Net-(U32-CANL)") (class "Default")
      (node (ref "R30") (pin "1") (pinfunction "1_1") (pintype "passive"))
      (node (ref "R32") (pin "2") (pinfunction "2_2") (pintype "passive"))
      (node (ref "U32") (pin "6") (pinfunction "CANL_6") (pintype "passive"))
      (node (ref "U33") (pin "2") (pinfunction "CAN1-L_2") (pintype "passive"))
      (node (ref "U34") (pin "2") (pinfunction "CAN1-L_2") (pintype "passive"))
    )
    (net (code "64") (name "VCC") (class "Default")
      (node (ref "C1") (pin "1") (pinfunction "1_1") (pintype "passive"))
      (node (ref "C10") (pin "1") (pinfunction "1_1") (pintype "passive"))
      (node (ref "C13") (pin "1") (pinfunction "1_1") (pintype "passive"))
      (node (ref "C14") (pin "2") (pinfunction "2_2") (pintype "passive"))
      (node (ref "C15") (pin "2") (pinfunction "2_2") (pintype "passive"))
      (node (ref "C16") (pin "2") (pinfunction "2_2") (pintype "passive"))
      (node (ref "C17") (pin "1") (pinfunction "1_1") (pintype "passive"))
      (node (ref "C3") (pin "1") (pinfunction "1_1") (pintype "passive"))
      (node (ref "C5") (pin "1") (pinfunction "1_1") (pintype "passive"))
      (node (ref "C6") (pin "1") (pinfunction "1_1") (pintype "passive"))
      (node (ref "C7") (pin "1") (pinfunction "1_1") (pintype "passive"))
      (node (ref "C8") (pin "1") (pinfunction "1_1") (pintype "passive"))
      (node (ref "C9") (pin "1") (pinfunction "1_1") (pintype "passive"))
      (node (ref "D2") (pin "5") (pinfunction "5_5") (pintype "passive"))
      (node (ref "J3") (pin "6") (pinfunction "6_6") (pintype "passive"))
      (node (ref "L1") (pin "1") (pinfunction "1_1") (pintype "passive"))
      (node (ref "R1") (pin "2") (pinfunction "2_2") (pintype "passive"))
      (node (ref "R5") (pin "1") (pinfunction "1_1") (pintype "passive"))
      (node (ref "R6") (pin "1") (pinfunction "1_1") (pintype "passive"))
      (node (ref "R7") (pin "1") (pinfunction "1_1") (pintype "passive"))
      (node (ref "R8") (pin "1") (pinfunction "1_1") (pintype "passive"))
      (node (ref "U1") (pin "4") (pinfunction "V+_4") (pintype "passive"))
      (node (ref "U1") (pin "5") (pinfunction "ADD0_5") (pintype "passive"))
      (node (ref "U12") (pin "5") (pinfunction "VCC_5") (pintype "passive"))
      (node (ref "U13") (pin "5") (pinfunction "VCC_5") (pintype "passive"))
      (node (ref "U14") (pin "2") (pinfunction "A_2") (pintype "passive"))
      (node (ref "U14") (pin "5") (pinfunction "VCC_5") (pintype "passive"))
      (node (ref "U17") (pin "5") (pinfunction "VCC_5") (pintype "passive"))
      (node (ref "U28") (pin "19") (pinfunction "VDD_19") (pintype "passive"))
      (node (ref "U28") (pin "32") (pinfunction "VDD_32") (pintype "passive"))
      (node (ref "U28") (pin "48") (pinfunction "VDDUSB_48") (pintype "passive"))
      (node (ref "U28") (pin "64") (pinfunction "VDD_64") (pintype "passive"))
      (node (ref "U3") (pin "1") (pinfunction "1_1") (pintype "passive"))
      (node (ref "U32") (pin "3") (pinfunction "VCC_3") (pintype "passive"))
      (node (ref "U6") (pin "8") (pinfunction "VCC_8") (pintype "passive"))
      (node (ref "U7") (pin "4") (pinfunction "FB/ADJ_4") (pintype "passive"))
    )
    (net (code "65") (name "unconnected-(J1-Pad12)") (class "Default")
      (node (ref "J1") (pin "12") (pinfunction "12_12") (pintype "passive"))
    )
    (net (code "66") (name "unconnected-(J1-PadG1)") (class "Default")
      (node (ref "J1") (pin "G1") (pinfunction "G1_G1") (pintype "passive"))
    )
    (net (code "67") (name "unconnected-(J1-PadG2)") (class "Default")
      (node (ref "J1") (pin "G2") (pinfunction "G2_G2") (pintype "passive"))
    )
    (net (code "68") (name "unconnected-(J2-Pad12)") (class "Default")
      (node (ref "J2") (pin "12") (pinfunction "12_12") (pintype "passive"))
    )
    (net (code "69") (name "unconnected-(J2-PadG1)") (class "Default")
      (node (ref "J2") (pin "G1") (pinfunction "G1_G1") (pintype "passive"))
    )
    (net (code "70") (name "unconnected-(J2-PadG2)") (class "Default")
      (node (ref "J2") (pin "G2") (pinfunction "G2_G2") (pintype "passive"))
    )
    (net (code "71") (name "unconnected-(U1-ADD1-Pad3)") (class "Default")
      (node (ref "U1") (pin "3") (pinfunction "ADD1_3") (pintype "passive+no_connect"))
    )
    (net (code "72") (name "unconnected-(U4-D+-Pad3)") (class "Default")
      (node (ref "U4") (pin "3") (pinfunction "D+_3") (pintype "passive"))
    )
    (net (code "73") (name "unconnected-(U4-D--Pad2)") (class "Default")
      (node (ref "U4") (pin "2") (pinfunction "D-_2") (pintype "passive"))
    )
    (net (code "74") (name "unconnected-(U4-ID-Pad4)") (class "Default")
      (node (ref "U4") (pin "4") (pinfunction "ID_4") (pintype "passive+no_connect"))
    )
    (net (code "75") (name "unconnected-(U12-NC-Pad1)") (class "Default")
      (node (ref "U12") (pin "1") (pinfunction "NC_1") (pintype "passive+no_connect"))
    )
    (net (code "76") (name "unconnected-(U13-NC-Pad1)") (class "Default")
      (node (ref "U13") (pin "1") (pinfunction "NC_1") (pintype "passive+no_connect"))
    )
    (net (code "77") (name "unconnected-(U17-NC-Pad1)") (class "Default")
      (node (ref "U17") (pin "1") (pinfunction "NC_1") (pintype "passive+no_connect"))
    )
    (net (code "78") (name "unconnected-(U28-PA0-Pad14)") (class "Default")
      (node (ref "U28") (pin "14") (pinfunction "PA0_14") (pintype "passive"))
    )
    (net (code "79") (name "unconnected-(U28-PA1-Pad15)") (class "Default")
      (node (ref "U28") (pin "15") (pinfunction "PA1_15") (pintype "passive"))
    )
    (net (code "80") (name "unconnected-(U28-PA4-Pad20)") (class "Default")
      (node (ref "U28") (pin "20") (pinfunction "PA4_20") (pintype "passive"))
    )
    (net (code "81") (name "unconnected-(U28-PA13-Pad46)") (class "Default")
      (node (ref "U28") (pin "46") (pinfunction "PA13_46") (pintype "passive"))
    )
    (net (code "82") (name "unconnected-(U28-PA14-Pad49)") (class "Default")
      (node (ref "U28") (pin "49") (pinfunction "PA14_49") (pintype "passive"))
    )
    (net (code "83") (name "unconnected-(U28-PB3-Pad55)") (class "Default")
      (node (ref "U28") (pin "55") (pinfunction "PB3_55") (pintype "passive"))
    )
    (net (code "84") (name "unconnected-(U28-PB4-Pad56)") (class "Default")
      (node (ref "U28") (pin "56") (pinfunction "PB4_56") (pintype "passive"))
    )
    (net (code "85") (name "unconnected-(U28-PB8-Pad61)") (class "Default")
      (node (ref "U28") (pin "61") (pinfunction "PB8_61") (pintype "passive"))
    )
    (net (code "86") (name "unconnected-(U28-PB9-Pad62)") (class "Default")
      (node (ref "U28") (pin "62") (pinfunction "PB9_62") (pintype "passive"))
    )
    (net (code "87") (name "unconnected-(U28-PB12-Pad33)") (class "Default")
      (node (ref "U28") (pin "33") (pinfunction "PB12_33") (pintype "passive"))
    )
    (net (code "88") (name "unconnected-(U28-PB13-Pad34)") (class "Default")
      (node (ref "U28") (pin "34") (pinfunction "PB13_34") (pintype "passive"))
    )
    (net (code "89") (name "unconnected-(U28-PB14-Pad35)") (class "Default")
      (node (ref "U28") (pin "35") (pinfunction "PB14_35") (pintype "passive"))
    )
    (net (code "90") (name "unconnected-(U28-PB15-Pad36)") (class "Default")
      (node (ref "U28") (pin "36") (pinfunction "PB15_36") (pintype "passive"))
    )
    (net (code "91") (name "unconnected-(U28-PC0-Pad8)") (class "Default")
      (node (ref "U28") (pin "8") (pinfunction "PC0_8") (pintype "passive"))
    )
    (net (code "92") (name "unconnected-(U28-PC1-Pad9)") (class "Default")
      (node (ref "U28") (pin "9") (pinfunction "PC1_9") (pintype "passive"))
    )
    (net (code "93") (name "unconnected-(U28-PC2-Pad10)") (class "Default")
      (node (ref "U28") (pin "10") (pinfunction "PC2_10") (pintype "passive"))
    )
    (net (code "94") (name "unconnected-(U28-PC3-Pad11)") (class "Default")
      (node (ref "U28") (pin "11") (pinfunction "PC3_11") (pintype "passive"))
    )
    (net (code "95") (name "unconnected-(U28-PC6-Pad37)") (class "Default")
      (node (ref "U28") (pin "37") (pinfunction "PC6_37") (pintype "passive"))
    )
    (net (code "96") (name "unconnected-(U28-PC7-Pad38)") (class "Default")
      (node (ref "U28") (pin "38") (pinfunction "PC7_38") (pintype "passive"))
    )
    (net (code "97") (name "unconnected-(U28-PC8-Pad39)") (class "Default")
      (node (ref "U28") (pin "39") (pinfunction "PC8_39") (pintype "passive"))
    )
    (net (code "98") (name "unconnected-(U28-PC9-Pad40)") (class "Default")
      (node (ref "U28") (pin "40") (pinfunction "PC9_40") (pintype "passive"))
    )
    (net (code "99") (name "unconnected-(U28-PC10-Pad51)") (class "Default")
      (node (ref "U28") (pin "51") (pinfunction "PC10_51") (pintype "passive"))
    )
    (net (code "100") (name "unconnected-(U28-PC11-Pad52)") (class "Default")
      (node (ref "U28") (pin "52") (pinfunction "PC11_52") (pintype "passive"))
    )
    (net (code "101") (name "unconnected-(U28-PC12-Pad53)") (class "Default")
      (node (ref "U28") (pin "53") (pinfunction "PC12_53") (pintype "passive"))
    )
    (net (code "102") (name "unconnected-(U28-PC13-Pad2)") (class "Default")
      (node (ref "U28") (pin "2") (pinfunction "PC13_2") (pintype "passive"))
    )
    (net (code "103") (name "unconnected-(U28-PC14{slash}OSC32_IN-Pad3)") (class "Default")
      (node (ref "U28") (pin "3") (pinfunction "PC14/OSC32_IN_3") (pintype "passive"))
    )
    (net (code "104") (name "unconnected-(U28-PC15{slash}OSC32_OUT-Pad4)") (class "Default")
      (node (ref "U28") (pin "4") (pinfunction "PC15/OSC32_OUT_4") (pintype "passive"))
    )
    (net (code "105") (name "unconnected-(U28-PD2-Pad54)") (class "Default")
      (node (ref "U28") (pin "54") (pinfunction "PD2_54") (pintype "passive"))
    )
    (net (code "106") (name "unconnected-(U28-PH0{slash}OSCIN-Pad5)") (class "Default")
      (node (ref "U28") (pin "5") (pinfunction "PH0/OSCIN_5") (pintype "passive"))
    )
    (net (code "107") (name "unconnected-(U28-PH1{slash}OSCOUT-Pad6)") (class "Default")
      (node (ref "U28") (pin "6") (pinfunction "PH1/OSCOUT_6") (pintype "passive"))
    )
    (net (code "108") (name "unconnected-(U28-PH3-BOOT0-Pad60)") (class "Default")
      (node (ref "U28") (pin "60") (pinfunction "PH3-BOOT0_60") (pintype "passive"))
    )
    (net (code "109") (name "unconnected-(U31-AnalogIP0-Pad96)") (class "Default")
      (node (ref "U31") (pin "96") (pinfunction "AnalogIP0_96") (pintype "passive"))
    )
    (net (code "110") (name "unconnected-(U31-AnalogIP1-Pad94)") (class "Default")
      (node (ref "U31") (pin "94") (pinfunction "AnalogIP1_94") (pintype "passive"))
    )
    (net (code "111") (name "unconnected-(U31-BT_nDisable-Pad91)") (class "Default")
      (node (ref "U31") (pin "91") (pinfunction "BT_nDisable_91") (pintype "passive"))
    )
    (net (code "112") (name "unconnected-(U31-CAM1_D2_N-Pad133)") (class "Default")
      (node (ref "U31") (pin "133") (pinfunction "CAM1_D2_N_133") (pintype "passive"))
    )
    (net (code "113") (name "unconnected-(U31-CAM1_D2_P-Pad135)") (class "Default")
      (node (ref "U31") (pin "135") (pinfunction "CAM1_D2_P_135") (pintype "passive"))
    )
    (net (code "114") (name "unconnected-(U31-CAM1_D3_N-Pad139)") (class "Default")
      (node (ref "U31") (pin "139") (pinfunction "CAM1_D3_N_139") (pintype "passive"))
    )
    (net (code "115") (name "unconnected-(U31-CAM1_D3_P-Pad141)") (class "Default")
      (node (ref "U31") (pin "141") (pinfunction "CAM1_D3_P_141") (pintype "passive"))
    )
    (net (code "116") (name "unconnected-(U31-CM4_1.8V-Pad88)") (class "Default")
      (node (ref "U31") (pin "88") (pinfunction "CM4_1.8V_88") (pintype "passive"))
    )
    (net (code "117") (name "unconnected-(U31-CM4_1.8V-Pad90)") (class "Default")
      (node (ref "U31") (pin "90") (pinfunction "CM4_1.8V_90") (pintype "passive"))
    )
    (net (code "118") (name "unconnected-(U31-DSI0_C_N-Pad169)") (class "Default")
      (node (ref "U31") (pin "169") (pinfunction "DSI0_C_N_169") (pintype "passive"))
    )
    (net (code "119") (name "unconnected-(U31-DSI0_C_P-Pad171)") (class "Default")
      (node (ref "U31") (pin "171") (pinfunction "DSI0_C_P_171") (pintype "passive"))
    )
    (net (code "120") (name "unconnected-(U31-DSI0_D0_N-Pad157)") (class "Default")
      (node (ref "U31") (pin "157") (pinfunction "DSI0_D0_N_157") (pintype "passive"))
    )
    (net (code "121") (name "unconnected-(U31-DSI0_D0_P-Pad159)") (class "Default")
      (node (ref "U31") (pin "159") (pinfunction "DSI0_D0_P_159") (pintype "passive"))
    )
    (net (code "122") (name "unconnected-(U31-DSI0_D1_N-Pad163)") (class "Default")
      (node (ref "U31") (pin "163") (pinfunction "DSI0_D1_N_163") (pintype "passive"))
    )
    (net (code "123") (name "unconnected-(U31-DSI0_D1_P-Pad165)") (class "Default")
      (node (ref "U31") (pin "165") (pinfunction "DSI0_D1_P_165") (pintype "passive"))
    )
    (net (code "124") (name "unconnected-(U31-DSI1_C_N-Pad187)") (class "Default")
      (node (ref "U31") (pin "187") (pinfunction "DSI1_C_N_187") (pintype "passive"))
    )
    (net (code "125") (name "unconnected-(U31-DSI1_C_P-Pad189)") (class "Default")
      (node (ref "U31") (pin "189") (pinfunction "DSI1_C_P_189") (pintype "passive"))
    )
    (net (code "126") (name "unconnected-(U31-DSI1_D0_N-Pad175)") (class "Default")
      (node (ref "U31") (pin "175") (pinfunction "DSI1_D0_N_175") (pintype "passive"))
    )
    (net (code "127") (name "unconnected-(U31-DSI1_D0_P-Pad177)") (class "Default")
      (node (ref "U31") (pin "177") (pinfunction "DSI1_D0_P_177") (pintype "passive"))
    )
    (net (code "128") (name "unconnected-(U31-DSI1_D1_N-Pad181)") (class "Default")
      (node (ref "U31") (pin "181") (pinfunction "DSI1_D1_N_181") (pintype "passive"))
    )
    (net (code "129") (name "unconnected-(U31-DSI1_D1_P-Pad183)") (class "Default")
      (node (ref "U31") (pin "183") (pinfunction "DSI1_D1_P_183") (pintype "passive"))
    )
    (net (code "130") (name "unconnected-(U31-DSI1_D2_N-Pad193)") (class "Default")
      (node (ref "U31") (pin "193") (pinfunction "DSI1_D2_N_193") (pintype "passive"))
    )
    (net (code "131") (name "unconnected-(U31-DSI1_D2_P-Pad195)") (class "Default")
      (node (ref "U31") (pin "195") (pinfunction "DSI1_D2_P_195") (pintype "passive"))
    )
    (net (code "132") (name "unconnected-(U31-DSI_D3_N-Pad194)") (class "Default")
      (node (ref "U31") (pin "194") (pinfunction "DSI_D3_N_194") (pintype "passive"))
    )
    (net (code "133") (name "unconnected-(U31-DSI_D3_P-Pad196)") (class "Default")
      (node (ref "U31") (pin "196") (pinfunction "DSI_D3_P_196") (pintype "passive"))
    )
    (net (code "134") (name "unconnected-(U31-EEPROM_nWP-Pad20)") (class "Default")
      (node (ref "U31") (pin "20") (pinfunction "EEPROM_nWP_20") (pintype "passive"))
    )
    (net (code "135") (name "unconnected-(U31-ETH_D0_N-Pad10)") (class "Default")
      (node (ref "U31") (pin "10") (pinfunction "ETH_D0_N_10") (pintype "passive"))
    )
    (net (code "136") (name "unconnected-(U31-ETH_D0_P-Pad12)") (class "Default")
      (node (ref "U31") (pin "12") (pinfunction "ETH_D0_P_12") (pintype "passive"))
    )
    (net (code "137") (name "unconnected-(U31-ETH_D1_N-Pad6)") (class "Default")
      (node (ref "U31") (pin "6") (pinfunction "ETH_D1_N_6") (pintype "passive"))
    )
    (net (code "138") (name "unconnected-(U31-ETH_D1_P-Pad4)") (class "Default")
      (node (ref "U31") (pin "4") (pinfunction "ETH_D1_P_4") (pintype "passive"))
    )
    (net (code "139") (name "unconnected-(U31-ETH_D2_N-Pad9)") (class "Default")
      (node (ref "U31") (pin "9") (pinfunction "ETH_D2_N_9") (pintype "passive"))
    )
    (net (code "140") (name "unconnected-(U31-ETH_D2_P-Pad11)") (class "Default")
      (node (ref "U31") (pin "11") (pinfunction "ETH_D2_P_11") (pintype "passive"))
    )
    (net (code "141") (name "unconnected-(U31-ETH_D3_N-Pad5)") (class "Default")
      (node (ref "U31") (pin "5") (pinfunction "ETH_D3_N_5") (pintype "passive"))
    )
    (net (code "142") (name "unconnected-(U31-ETH_D3_P-Pad3)") (class "Default")
      (node (ref "U31") (pin "3") (pinfunction "ETH_D3_P_3") (pintype "passive"))
    )
    (net (code "143") (name "unconnected-(U31-ETH_SYNC_IN-Pad16)") (class "Default")
      (node (ref "U31") (pin "16") (pinfunction "ETH_SYNC_IN_16") (pintype "passive"))
    )
    (net (code "144") (name "unconnected-(U31-ETH_SYNC_OUT-Pad18)") (class "Default")
      (node (ref "U31") (pin "18") (pinfunction "ETH_SYNC_OUT_18") (pintype "passive"))
    )
    (net (code "145") (name "unconnected-(U31-ETH_nLED1-Pad19)") (class "Default")
      (node (ref "U31") (pin "19") (pinfunction "ETH_nLED1_19") (pintype "passive"))
    )
    (net (code "146") (name "unconnected-(U31-ETH_nLED2-Pad17)") (class "Default")
      (node (ref "U31") (pin "17") (pinfunction "ETH_nLED2_17") (pintype "passive"))
    )
    (net (code "147") (name "unconnected-(U31-ETH_nLED3-Pad15)") (class "Default")
      (node (ref "U31") (pin "15") (pinfunction "ETH_nLED3_15") (pintype "passive"))
    )
    (net (code "148") (name "unconnected-(U31-GLOBAL_EN-Pad99)") (class "Default")
      (node (ref "U31") (pin "99") (pinfunction "GLOBAL_EN_99") (pintype "passive"))
    )
    (net (code "149") (name "unconnected-(U31-GND-Pad144)") (class "Default")
      (node (ref "U31") (pin "144") (pinfunction "GND_144") (pintype "passive"))
    )
    (net (code "150") (name "unconnected-(U31-GPIO2-Pad58)") (class "Default")
      (node (ref "U31") (pin "58") (pinfunction "GPIO2_58") (pintype "passive"))
    )
    (net (code "151") (name "unconnected-(U31-GPIO4-Pad54)") (class "Default")
      (node (ref "U31") (pin "54") (pinfunction "GPIO4_54") (pintype "passive"))
    )
    (net (code "152") (name "unconnected-(U31-GPIO5-Pad34)") (class "Default")
      (node (ref "U31") (pin "34") (pinfunction "GPIO5_34") (pintype "passive"))
    )
    (net (code "153") (name "unconnected-(U31-GPIO6-Pad30)") (class "Default")
      (node (ref "U31") (pin "30") (pinfunction "GPIO6_30") (pintype "passive"))
    )
    (net (code "154") (name "unconnected-(U31-GPIO7-Pad37)") (class "Default")
      (node (ref "U31") (pin "37") (pinfunction "GPIO7_37") (pintype "passive"))
    )
    (net (code "155") (name "unconnected-(U31-GPIO8-Pad39)") (class "Default")
      (node (ref "U31") (pin "39") (pinfunction "GPIO8_39") (pintype "passive"))
    )
    (net (code "156") (name "unconnected-(U31-GPIO9-Pad40)") (class "Default")
      (node (ref "U31") (pin "40") (pinfunction "GPIO9_40") (pintype "passive"))
    )
    (net (code "157") (name "unconnected-(U31-GPIO10-Pad44)") (class "Default")
      (node (ref "U31") (pin "44") (pinfunction "GPIO10_44") (pintype "passive"))
    )
    (net (code "158") (name "unconnected-(U31-GPIO11-Pad38)") (class "Default")
      (node (ref "U31") (pin "38") (pinfunction "GPIO11_38") (pintype "passive"))
    )
    (net (code "159") (name "unconnected-(U31-GPIO12-Pad31)") (class "Default")
      (node (ref "U31") (pin "31") (pinfunction "GPIO12_31") (pintype "passive"))
    )
    (net (code "160") (name "unconnected-(U31-GPIO13-Pad28)") (class "Default")
      (node (ref "U31") (pin "28") (pinfunction "GPIO13_28") (pintype "passive"))
    )
    (net (code "161") (name "unconnected-(U31-GPIO16-Pad29)") (class "Default")
      (node (ref "U31") (pin "29") (pinfunction "GPIO16_29") (pintype "passive"))
    )
    (net (code "162") (name "unconnected-(U31-GPIO17-Pad50)") (class "Default")
      (node (ref "U31") (pin "50") (pinfunction "GPIO17_50") (pintype "passive"))
    )
    (net (code "163") (name "unconnected-(U31-GPIO18-Pad49)") (class "Default")
      (node (ref "U31") (pin "49") (pinfunction "GPIO18_49") (pintype "passive"))
    )
    (net (code "164") (name "unconnected-(U31-GPIO19-Pad26)") (class "Default")
      (node (ref "U31") (pin "26") (pinfunction "GPIO19_26") (pintype "passive"))
    )
    (net (code "165") (name "unconnected-(U31-GPIO20-Pad27)") (class "Default")
      (node (ref "U31") (pin "27") (pinfunction "GPIO20_27") (pintype "passive"))
    )
    (net (code "166") (name "unconnected-(U31-GPIO21-Pad25)") (class "Default")
      (node (ref "U31") (pin "25") (pinfunction "GPIO21_25") (pintype "passive"))
    )
    (net (code "167") (name "unconnected-(U31-GPIO22-Pad46)") (class "Default")
      (node (ref "U31") (pin "46") (pinfunction "GPIO22_46") (pintype "passive"))
    )
    (net (code "168") (name "unconnected-(U31-GPIO23-Pad47)") (class "Default")
      (node (ref "U31") (pin "47") (pinfunction "GPIO23_47") (pintype "passive"))
    )
    (net (code "169") (name "unconnected-(U31-GPIO24-Pad45)") (class "Default")
      (node (ref "U31") (pin "45") (pinfunction "GPIO24_45") (pintype "passive"))
    )
    (net (code "170") (name "unconnected-(U31-GPIO25-Pad41)") (class "Default")
      (node (ref "U31") (pin "41") (pinfunction "GPIO25_41") (pintype "passive"))
    )
    (net (code "171") (name "unconnected-(U31-GPIO26-Pad24)") (class "Default")
      (node (ref "U31") (pin "24") (pinfunction "GPIO26_24") (pintype "passive"))
    )
    (net (code "172") (name "unconnected-(U31-GPIO27-Pad48)") (class "Default")
      (node (ref "U31") (pin "48") (pinfunction "GPIO27_48") (pintype "passive"))
    )
    (net (code "173") (name "unconnected-(U31-HDMI0_CEC-Pad151)") (class "Default")
      (node (ref "U31") (pin "151") (pinfunction "HDMI0_CEC_151") (pintype "passive"))
    )
    (net (code "174") (name "unconnected-(U31-HDMI0_CLK_N-Pad190)") (class "Default")
      (node (ref "U31") (pin "190") (pinfunction "HDMI0_CLK_N_190") (pintype "passive"))
    )
    (net (code "175") (name "unconnected-(U31-HDMI0_CLK_P-Pad188)") (class "Default")
      (node (ref "U31") (pin "188") (pinfunction "HDMI0_CLK_P_188") (pintype "passive"))
    )
    (net (code "176") (name "unconnected-(U31-HDMI0_HPD-Pad153)") (class "Default")
      (node (ref "U31") (pin "153") (pinfunction "HDMI0_HPD_153") (pintype "passive"))
    )
    (net (code "177") (name "unconnected-(U31-HDMI0_SCL-Pad200)") (class "Default")
      (node (ref "U31") (pin "200") (pinfunction "HDMI0_SCL_200") (pintype "passive"))
    )
    (net (code "178") (name "unconnected-(U31-HDMI0_SDA-Pad199)") (class "Default")
      (node (ref "U31") (pin "199") (pinfunction "HDMI0_SDA_199") (pintype "passive"))
    )
    (net (code "179") (name "unconnected-(U31-HDMI0_TX0_N-Pad184)") (class "Default")
      (node (ref "U31") (pin "184") (pinfunction "HDMI0_TX0_N_184") (pintype "passive"))
    )
    (net (code "180") (name "unconnected-(U31-HDMI0_TX0_P-Pad182)") (class "Default")
      (node (ref "U31") (pin "182") (pinfunction "HDMI0_TX0_P_182") (pintype "passive"))
    )
    (net (code "181") (name "unconnected-(U31-HDMI0_TX1_N-Pad178)") (class "Default")
      (node (ref "U31") (pin "178") (pinfunction "HDMI0_TX1_N_178") (pintype "passive"))
    )
    (net (code "182") (name "unconnected-(U31-HDMI0_TX1_P-Pad176)") (class "Default")
      (node (ref "U31") (pin "176") (pinfunction "HDMI0_TX1_P_176") (pintype "passive"))
    )
    (net (code "183") (name "unconnected-(U31-HDMI0_TX2_N-Pad172)") (class "Default")
      (node (ref "U31") (pin "172") (pinfunction "HDMI0_TX2_N_172") (pintype "passive"))
    )
    (net (code "184") (name "unconnected-(U31-HDMI0_TX2_P-Pad170)") (class "Default")
      (node (ref "U31") (pin "170") (pinfunction "HDMI0_TX2_P_170") (pintype "passive"))
    )
    (net (code "185") (name "unconnected-(U31-HDMI1_CEC-Pad149)") (class "Default")
      (node (ref "U31") (pin "149") (pinfunction "HDMI1_CEC_149") (pintype "passive"))
    )
    (net (code "186") (name "unconnected-(U31-HDMI1_CLK_N-Pad166)") (class "Default")
      (node (ref "U31") (pin "166") (pinfunction "HDMI1_CLK_N_166") (pintype "passive"))
    )
    (net (code "187") (name "unconnected-(U31-HDMI1_CLK_P-Pad164)") (class "Default")
      (node (ref "U31") (pin "164") (pinfunction "HDMI1_CLK_P_164") (pintype "passive"))
    )
    (net (code "188") (name "unconnected-(U31-HDMI1_HPD-Pad143)") (class "Default")
      (node (ref "U31") (pin "143") (pinfunction "HDMI1_HPD_143") (pintype "passive"))
    )
    (net (code "189") (name "unconnected-(U31-HDMI1_SCL-Pad147)") (class "Default")
      (node (ref "U31") (pin "147") (pinfunction "HDMI1_SCL_147") (pintype "passive"))
    )
    (net (code "190") (name "unconnected-(U31-HDMI1_SDA-Pad145)") (class "Default")
      (node (ref "U31") (pin "145") (pinfunction "HDMI1_SDA_145") (pintype "passive"))
    )
    (net (code "191") (name "unconnected-(U31-HDMI1_TX0_N-Pad160)") (class "Default")
      (node (ref "U31") (pin "160") (pinfunction "HDMI1_TX0_N_160") (pintype "passive"))
    )
    (net (code "192") (name "unconnected-(U31-HDMI1_TX0_P-Pad158)") (class "Default")
      (node (ref "U31") (pin "158") (pinfunction "HDMI1_TX0_P_158") (pintype "passive"))
    )
    (net (code "193") (name "unconnected-(U31-HDMI1_TX1_N-Pad154)") (class "Default")
      (node (ref "U31") (pin "154") (pinfunction "HDMI1_TX1_N_154") (pintype "passive"))
    )
    (net (code "194") (name "unconnected-(U31-HDMI1_TX1_P-Pad152)") (class "Default")
      (node (ref "U31") (pin "152") (pinfunction "HDMI1_TX1_P_152") (pintype "passive"))
    )
    (net (code "195") (name "unconnected-(U31-HDMI1_TX2_N-Pad148)") (class "Default")
      (node (ref "U31") (pin "148") (pinfunction "HDMI1_TX2_N_148") (pintype "passive"))
    )
    (net (code "196") (name "unconnected-(U31-HDMI1_TX2_P-Pad146)") (class "Default")
      (node (ref "U31") (pin "146") (pinfunction "HDMI1_TX2_P_146") (pintype "passive"))
    )
    (net (code "197") (name "unconnected-(U31-PCIe_CLK_N-Pad112)") (class "Default")
      (node (ref "U31") (pin "112") (pinfunction "PCIe_CLK_N_112") (pintype "passive"))
    )
    (net (code "198") (name "unconnected-(U31-PCIe_CLK_P-Pad110)") (class "Default")
      (node (ref "U31") (pin "110") (pinfunction "PCIe_CLK_P_110") (pintype "passive"))
    )
    (net (code "199") (name "unconnected-(U31-PCIe_CLK_nREQ-Pad102)") (class "Default")
      (node (ref "U31") (pin "102") (pinfunction "PCIe_CLK_nREQ_102") (pintype "passive"))
    )
    (net (code "200") (name "unconnected-(U31-PCIe_RX_N-Pad118)") (class "Default")
      (node (ref "U31") (pin "118") (pinfunction "PCIe_RX_N_118") (pintype "passive"))
    )
    (net (code "201") (name "unconnected-(U31-PCIe_RX_P-Pad116)") (class "Default")
      (node (ref "U31") (pin "116") (pinfunction "PCIe_RX_P_116") (pintype "passive"))
    )
    (net (code "202") (name "unconnected-(U31-PCIe_TX_N-Pad124)") (class "Default")
      (node (ref "U31") (pin "124") (pinfunction "PCIe_TX_N_124") (pintype "passive"))
    )
    (net (code "203") (name "unconnected-(U31-PCIe_TX_P-Pad122)") (class "Default")
      (node (ref "U31") (pin "122") (pinfunction "PCIe_TX_P_122") (pintype "passive"))
    )
    (net (code "204") (name "unconnected-(U31-PCIe_nRST-Pad109)") (class "Default")
      (node (ref "U31") (pin "109") (pinfunction "PCIe_nRST_109") (pintype "passive"))
    )
    (net (code "205") (name "unconnected-(U31-PI_nLED_ACTIVITY-Pad21)") (class "Default")
      (node (ref "U31") (pin "21") (pinfunction "PI_nLED_ACTIVITY_21") (pintype "passive"))
    )
    (net (code "206") (name "unconnected-(U31-Pi_LED_nPWR-Pad95)") (class "Default")
      (node (ref "U31") (pin "95") (pinfunction "Pi_LED_nPWR_95") (pintype "passive"))
    )
    (net (code "207") (name "unconnected-(U31-RESERVED-Pad76)") (class "Default")
      (node (ref "U31") (pin "76") (pinfunction "RESERVED_76") (pintype "passive"))
    )
    (net (code "208") (name "unconnected-(U31-RESERVED-Pad104)") (class "Default")
      (node (ref "U31") (pin "104") (pinfunction "RESERVED_104") (pintype "passive"))
    )
    (net (code "209") (name "unconnected-(U31-RESERVED-Pad106)") (class "Default")
      (node (ref "U31") (pin "106") (pinfunction "RESERVED_106") (pintype "passive"))
    )
    (net (code "210") (name "unconnected-(U31-RUN_PG-Pad92)") (class "Default")
      (node (ref "U31") (pin "92") (pinfunction "RUN_PG_92") (pintype "passive"))
    )
    (net (code "211") (name "unconnected-(U31-SD_CLK-Pad57)") (class "Default")
      (node (ref "U31") (pin "57") (pinfunction "SD_CLK_57") (pintype "passive"))
    )
    (net (code "212") (name "unconnected-(U31-SD_CMD-Pad62)") (class "Default")
      (node (ref "U31") (pin "62") (pinfunction "SD_CMD_62") (pintype "passive"))
    )
    (net (code "213") (name "unconnected-(U31-SD_DAT0-Pad63)") (class "Default")
      (node (ref "U31") (pin "63") (pinfunction "SD_DAT0_63") (pintype "passive"))
    )
    (net (code "214") (name "unconnected-(U31-SD_DAT1-Pad67)") (class "Default")
      (node (ref "U31") (pin "67") (pinfunction "SD_DAT1_67") (pintype "passive"))
    )
    (net (code "215") (name "unconnected-(U31-SD_DAT2-Pad69)") (class "Default")
      (node (ref "U31") (pin "69") (pinfunction "SD_DAT2_69") (pintype "passive"))
    )
    (net (code "216") (name "unconnected-(U31-SD_DAT3-Pad61)") (class "Default")
      (node (ref "U31") (pin "61") (pinfunction "SD_DAT3_61") (pintype "passive"))
    )
    (net (code "217") (name "unconnected-(U31-SD_DAT4-Pad68)") (class "Default")
      (node (ref "U31") (pin "68") (pinfunction "SD_DAT4_68") (pintype "passive"))
    )
    (net (code "218") (name "unconnected-(U31-SD_DAT5-Pad64)") (class "Default")
      (node (ref "U31") (pin "64") (pinfunction "SD_DAT5_64") (pintype "passive"))
    )
    (net (code "219") (name "unconnected-(U31-SD_DAT6-Pad72)") (class "Default")
      (node (ref "U31") (pin "72") (pinfunction "SD_DAT6_72") (pintype "passive"))
    )
    (net (code "220") (name "unconnected-(U31-SD_DAT7-Pad70)") (class "Default")
      (node (ref "U31") (pin "70") (pinfunction "SD_DAT7_70") (pintype "passive"))
    )
    (net (code "221") (name "unconnected-(U31-SD_PWR_ON-Pad75)") (class "Default")
      (node (ref "U31") (pin "75") (pinfunction "SD_PWR_ON_75") (pintype "passive"))
    )
    (net (code "222") (name "unconnected-(U31-SD_VDD_OVERIDE-Pad73)") (class "Default")
      (node (ref "U31") (pin "73") (pinfunction "SD_VDD_OVERIDE_73") (pintype "passive"))
    )
    (net (code "223") (name "unconnected-(U31-USB_N-Pad103)") (class "Default")
      (node (ref "U31") (pin "103") (pinfunction "USB_N_103") (pintype "passive"))
    )
    (net (code "224") (name "unconnected-(U31-USB_OTG_ID-Pad101)") (class "Default")
      (node (ref "U31") (pin "101") (pinfunction "USB_OTG_ID_101") (pintype "passive"))
    )
    (net (code "225") (name "unconnected-(U31-USB_P-Pad105)") (class "Default")
      (node (ref "U31") (pin "105") (pinfunction "USB_P_105") (pintype "passive"))
    )
    (net (code "226") (name "unconnected-(U31-VDAC_COMP-Pad111)") (class "Default")
      (node (ref "U31") (pin "111") (pinfunction "VDAC_COMP_111") (pintype "passive"))
    )
    (net (code "227") (name "unconnected-(U31-nEXTRST-Pad100)") (class "Default")
      (node (ref "U31") (pin "100") (pinfunction "nEXTRST_100") (pintype "passive"))
    )
    (net (code "228") (name "unconnected-(U31-nRPIBOOT-Pad93)") (class "Default")
      (node (ref "U31") (pin "93") (pinfunction "nRPIBOOT_93") (pintype "passive"))
    )
    (net (code "229") (name "unconnected-(U33-CAN2-H-Pad3)") (class "Default")
      (node (ref "U33") (pin "3") (pinfunction "CAN2-H_3") (pintype "passive"))
    )
    (net (code "230") (name "unconnected-(U33-CAN2-L-Pad4)") (class "Default")
      (node (ref "U33") (pin "4") (pinfunction "CAN2-L_4") (pintype "passive"))
    )
    (net (code "231") (name "unconnected-(U34-CAN2-H-Pad3)") (class "Default")
      (node (ref "U34") (pin "3") (pinfunction "CAN2-H_3") (pintype "passive"))
    )
    (net (code "232") (name "unconnected-(U34-CAN2-L-Pad4)") (class "Default")
      (node (ref "U34") (pin "4") (pinfunction "CAN2-L_4") (pintype "passive"))
    )
  )
)
